# microInv_batt_controller.net
KiCad netlist of a schematic drawn in Altium Designer
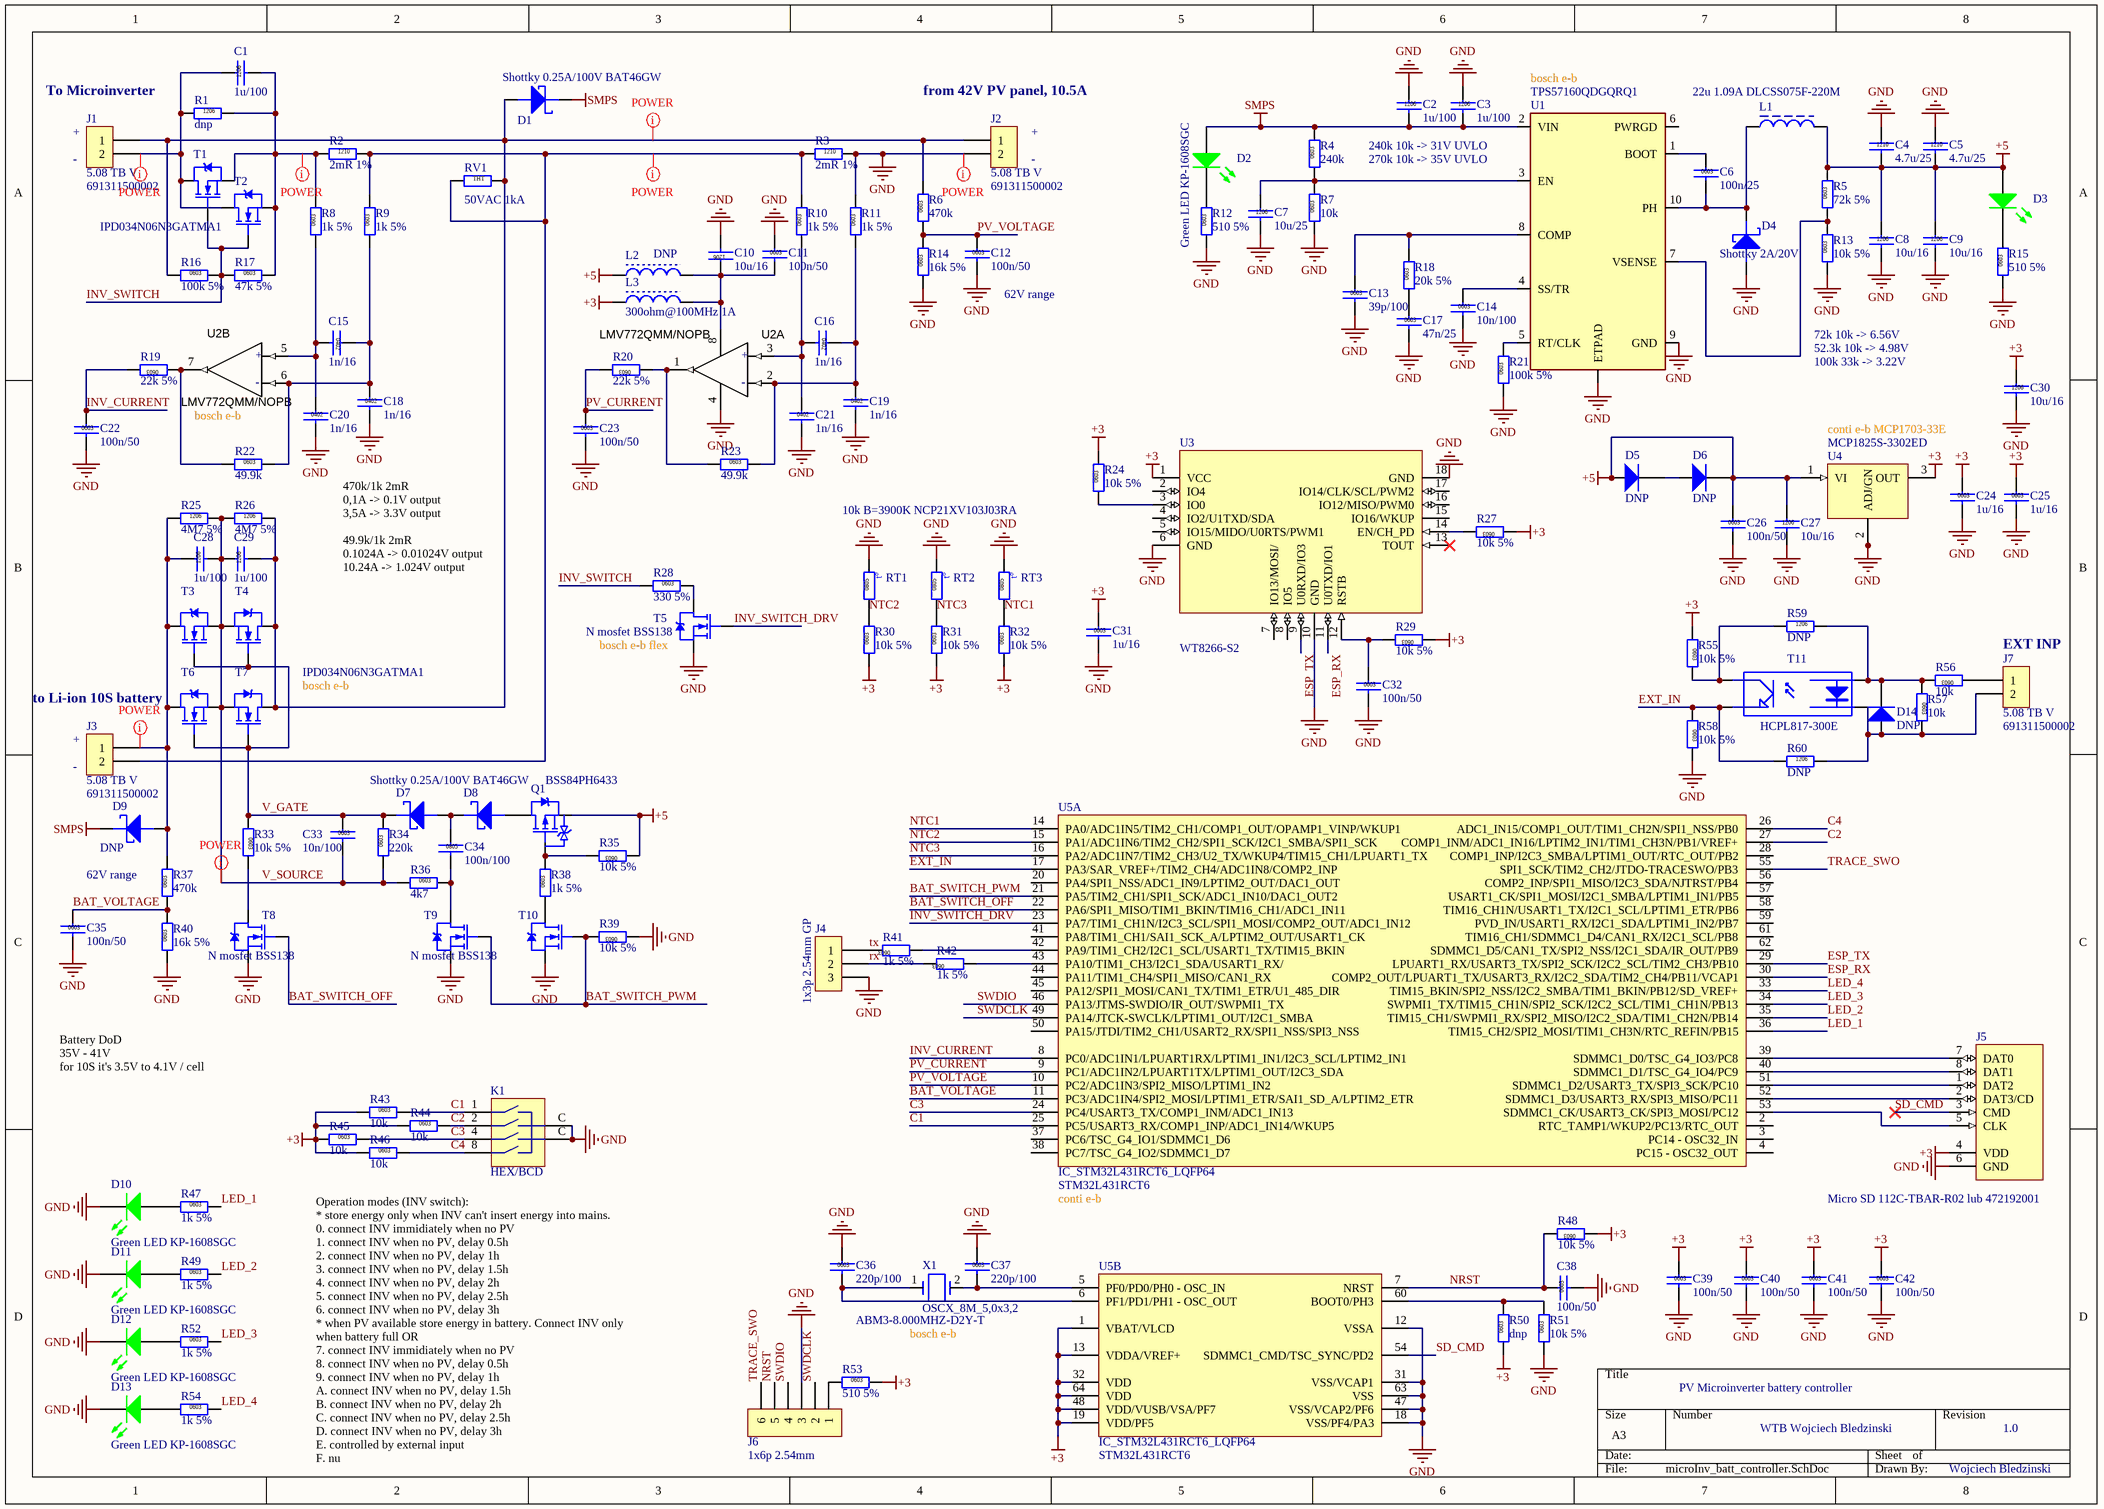
[diagram p0: microInv_batt_controller.SchDoc]

(export (version "E")
  (design (tool "Eeschema 10.0.6"))
  (components
    (comp (ref "C1")
      (value "1u/100")
      (footprint "CAP_1206")
      (description "X7R chip capacitor")
      (fields (field (name "MANUFACTURER") "AVX") (field (name "MANUFACTURER PART NUMBER") "12061C105KAT2A"))
      (libsource (lib "WB") (part "CAP_B_1u_100_1206_X7R"))
    )
    (comp (ref "C2")
      (value "1u/100")
      (footprint "CAP_1206")
      (description "X7R chip capacitor")
      (fields (field (name "MANUFACTURER") "AVX") (field (name "MANUFACTURER PART NUMBER") "12061C105KAT2A"))
      (libsource (lib "WB") (part "CAP_B_1u_100_1206_X7R"))
    )
    (comp (ref "C3")
      (value "1u/100")
      (footprint "CAP_1206")
      (description "X7R chip capacitor")
      (fields (field (name "MANUFACTURER") "AVX") (field (name "MANUFACTURER PART NUMBER") "12061C105KAT2A"))
      (libsource (lib "WB") (part "CAP_B_1u_100_1206_X7R"))
    )
    (comp (ref "C4")
      (value "4.7u/25")
      (footprint "CAP_1210")
      (description "X5R chip capacitor")
      (fields
        (field (name "MANUFACTURER") "YAGEO")
        (field (name "MANUFACTURER PART NUMBER") "CC1210KKX5R8BB475")
      )
      (libsource (lib "WB") (part "CAP_B_4.7u_25_1210_X5R"))
    )
    (comp (ref "C5")
      (value "4.7u/25")
      (footprint "CAP_1210")
      (description "X5R chip capacitor")
      (fields
        (field (name "MANUFACTURER") "YAGEO")
        (field (name "MANUFACTURER PART NUMBER") "CC1210KKX5R8BB475")
      )
      (libsource (lib "WB") (part "CAP_B_4.7u_25_1210_X5R"))
    )
    (comp (ref "C6")
      (value "100n/25")
      (footprint "CAP_0603")
      (description "X7R chip capacitor")
      (fields
        (field (name "MANUFACTURER") "SAMSUNG")
        (field (name "MANUFACTURER PART NUMBER") "CL10B104KB8NNNC")
      )
      (libsource (lib "WB") (part "CAP_B_100n_50_0603_X7R"))
    )
    (comp (ref "C7")
      (value "10u/25")
      (footprint "CAP_1206")
      (description "X5R chip capacitor")
      (fields
        (field (name "MANUFACTURER") "SAMSUNG")
        (field (name "MANUFACTURER PART NUMBER") "CL31A106KAHNNNE")
      )
      (libsource (lib "WB") (part "CAP_B_10u_25_1206_X5R"))
    )
    (comp (ref "C8")
      (value "10u/16")
      (footprint "CAP_1206")
      (description "X7R chip capacitor")
      (fields
        (field (name "MANUFACTURER") "KYOCERA")
        (field (name "MANUFACTURER PART NUMBER") "CM316X7R106K16AT")
      )
      (libsource (lib "WB") (part "CAP_B_10u_16_1206_X7R"))
    )
    (comp (ref "C9")
      (value "10u/16")
      (footprint "CAP_1206")
      (description "X7R chip capacitor")
      (fields
        (field (name "MANUFACTURER") "KYOCERA")
        (field (name "MANUFACTURER PART NUMBER") "CM316X7R106K16AT")
      )
      (libsource (lib "WB") (part "CAP_B_10u_16_1206_X7R"))
    )
    (comp (ref "C10")
      (value "10u/16")
      (footprint "CAP_1206")
      (description "X7R chip capacitor")
      (fields
        (field (name "MANUFACTURER") "KYOCERA")
        (field (name "MANUFACTURER PART NUMBER") "CM316X7R106K16AT")
      )
      (libsource (lib "WB") (part "CAP_B_10u_16_1206_X7R"))
    )
    (comp (ref "C11")
      (value "100n/50")
      (footprint "CAP_0603")
      (description "X7R chip capacitor")
      (fields
        (field (name "MANUFACTURER") "SAMSUNG")
        (field (name "MANUFACTURER PART NUMBER") "CL10B104KB8NNNC")
      )
      (libsource (lib "WB") (part "CAP_B_100n_50_0603_X7R"))
    )
    (comp (ref "C12")
      (value "100n/50")
      (footprint "CAP_0603")
      (description "X7R chip capacitor")
      (fields
        (field (name "MANUFACTURER") "SAMSUNG")
        (field (name "MANUFACTURER PART NUMBER") "CL10B104KB8NNNC")
      )
      (libsource (lib "WB") (part "CAP_B_100n_50_0603_X7R"))
    )
    (comp (ref "C13")
      (value "39p/100")
      (footprint "CAP_0603")
      (description "COG chip capacitor")
      (fields (field (name "TOLERANCE") "10%") (field (name "VOLTAGE") "100"))
      (libsource (lib "WB") (part "CAP_B_39p_100_0603_COG"))
    )
    (comp (ref "C14")
      (value "10n/100")
      (footprint "CAP_0603")
      (description "X7R chip capacitor")
      (fields
        (field (name "MANUFACTURER") "SAMSUNG")
        (field (name "MANUFACTURER PART NUMBER") "CL10B103KC8NNNC")
      )
      (libsource (lib "WB") (part "CAP_B_10n_100_0603_X7R"))
    )
    (comp (ref "C15")
      (value "1n/16")
      (footprint "CAP_0402_HD_IPC")
      (description "X7R chip capacitor")
      (fields
        (field (name "MANUFACTURER") "SAMSUNG")
        (field (name "MANUFACTURER PART NUMBER") "0402YC102KAT2A")
      )
      (libsource (lib "WB") (part "CAP_B_1n_16_0402_X7R"))
    )
    (comp (ref "C16")
      (value "1n/16")
      (footprint "CAP_0402_HD_IPC")
      (description "X7R chip capacitor")
      (fields
        (field (name "MANUFACTURER") "SAMSUNG")
        (field (name "MANUFACTURER PART NUMBER") "0402YC102KAT2A")
      )
      (libsource (lib "WB") (part "CAP_B_1n_16_0402_X7R"))
    )
    (comp (ref "C17")
      (value "47n/25")
      (footprint "CAP_0603")
      (description "X7R chip capacitor")
      (fields (field (name "TOLERANCE") "10%") (field (name "VOLTAGE") "25"))
      (libsource (lib "WB") (part "CAP_B_47n_25_0603_X7R"))
    )
    (comp (ref "C18")
      (value "1n/16")
      (footprint "CAP_0402_HD_IPC")
      (description "X7R chip capacitor")
      (fields
        (field (name "MANUFACTURER") "SAMSUNG")
        (field (name "MANUFACTURER PART NUMBER") "0402YC102KAT2A")
      )
      (libsource (lib "WB") (part "CAP_B_1n_16_0402_X7R"))
    )
    (comp (ref "C19")
      (value "1n/16")
      (footprint "CAP_0402_HD_IPC")
      (description "X7R chip capacitor")
      (fields
        (field (name "MANUFACTURER") "SAMSUNG")
        (field (name "MANUFACTURER PART NUMBER") "0402YC102KAT2A")
      )
      (libsource (lib "WB") (part "CAP_B_1n_16_0402_X7R"))
    )
    (comp (ref "C20")
      (value "1n/16")
      (footprint "CAP_0402_HD_IPC")
      (description "X7R chip capacitor")
      (fields
        (field (name "MANUFACTURER") "SAMSUNG")
        (field (name "MANUFACTURER PART NUMBER") "0402YC102KAT2A")
      )
      (libsource (lib "WB") (part "CAP_B_1n_16_0402_X7R"))
    )
    (comp (ref "C21")
      (value "1n/16")
      (footprint "CAP_0402_HD_IPC")
      (description "X7R chip capacitor")
      (fields
        (field (name "MANUFACTURER") "SAMSUNG")
        (field (name "MANUFACTURER PART NUMBER") "0402YC102KAT2A")
      )
      (libsource (lib "WB") (part "CAP_B_1n_16_0402_X7R"))
    )
    (comp (ref "C22")
      (value "100n/50")
      (footprint "CAP_0603")
      (description "X7R chip capacitor")
      (fields
        (field (name "MANUFACTURER") "SAMSUNG")
        (field (name "MANUFACTURER PART NUMBER") "CL10B104KB8NNNC")
      )
      (libsource (lib "WB") (part "CAP_B_100n_50_0603_X7R"))
    )
    (comp (ref "C23")
      (value "100n/50")
      (footprint "CAP_0603")
      (description "X7R chip capacitor")
      (fields
        (field (name "MANUFACTURER") "SAMSUNG")
        (field (name "MANUFACTURER PART NUMBER") "CL10B104KB8NNNC")
      )
      (libsource (lib "WB") (part "CAP_B_100n_50_0603_X7R"))
    )
    (comp (ref "C24")
      (value "1u/16")
      (footprint "CAP_0603")
      (description "X7R chip capacitor")
      (fields
        (field (name "MANUFACTURER") "SAMSUNG")
        (field (name "MANUFACTURER PART NUMBER") "CL10B105KO8NNNC")
      )
      (libsource (lib "WB") (part "CAP_B_1u_16_0603_X7R"))
    )
    (comp (ref "C25")
      (value "1u/16")
      (footprint "CAP_0603")
      (description "X7R chip capacitor")
      (fields
        (field (name "MANUFACTURER") "SAMSUNG")
        (field (name "MANUFACTURER PART NUMBER") "CL10B105KO8NNNC")
      )
      (libsource (lib "WB") (part "CAP_B_1u_16_0603_X7R"))
    )
    (comp (ref "C26")
      (value "100n/50")
      (footprint "CAP_0603")
      (description "X7R chip capacitor")
      (fields
        (field (name "MANUFACTURER") "SAMSUNG")
        (field (name "MANUFACTURER PART NUMBER") "CL10B104KB8NNNC")
      )
      (libsource (lib "WB") (part "CAP_B_100n_50_0603_X7R"))
    )
    (comp (ref "C27")
      (value "10u/16")
      (footprint "CAP_1206")
      (description "X7R chip capacitor")
      (fields
        (field (name "MANUFACTURER") "KYOCERA")
        (field (name "MANUFACTURER PART NUMBER") "CM316X7R106K16AT")
      )
      (libsource (lib "WB") (part "CAP_B_10u_16_1206_X7R"))
    )
    (comp (ref "C28")
      (value "1u/100")
      (footprint "CAP_1206")
      (description "X7R chip capacitor")
      (fields (field (name "MANUFACTURER") "AVX") (field (name "MANUFACTURER PART NUMBER") "12061C105KAT2A"))
      (libsource (lib "WB") (part "CAP_B_1u_100_1206_X7R"))
    )
    (comp (ref "C29")
      (value "1u/100")
      (footprint "CAP_1206")
      (description "X7R chip capacitor")
      (fields (field (name "MANUFACTURER") "AVX") (field (name "MANUFACTURER PART NUMBER") "12061C105KAT2A"))
      (libsource (lib "WB") (part "CAP_B_1u_100_1206_X7R"))
    )
    (comp (ref "C30")
      (value "10u/16")
      (footprint "CAP_1206")
      (description "X7R chip capacitor")
      (fields
        (field (name "MANUFACTURER") "KYOCERA")
        (field (name "MANUFACTURER PART NUMBER") "CM316X7R106K16AT")
      )
      (libsource (lib "WB") (part "CAP_B_10u_16_1206_X7R"))
    )
    (comp (ref "C31")
      (value "1u/16")
      (footprint "CAP_0603")
      (description "X7R chip capacitor")
      (fields
        (field (name "MANUFACTURER") "SAMSUNG")
        (field (name "MANUFACTURER PART NUMBER") "CL10B105KO8NNNC")
      )
      (libsource (lib "WB") (part "CAP_B_1u_16_0603_X7R"))
    )
    (comp (ref "C32")
      (value "100n/50")
      (footprint "CAP_0603")
      (description "X7R chip capacitor")
      (fields
        (field (name "MANUFACTURER") "SAMSUNG")
        (field (name "MANUFACTURER PART NUMBER") "CL10B104KB8NNNC")
      )
      (libsource (lib "WB") (part "CAP_B_100n_50_0603_X7R"))
    )
    (comp (ref "C33")
      (value "10n/100")
      (footprint "CAP_0603")
      (description "X7R chip capacitor")
      (fields
        (field (name "MANUFACTURER") "SAMSUNG")
        (field (name "MANUFACTURER PART NUMBER") "CL10B103KC8NNNC")
      )
      (libsource (lib "WB") (part "CAP_B_10n_100_0603_X7R"))
    )
    (comp (ref "C34")
      (value "100n/100")
      (footprint "CAP_0805")
      (description "X7R chip capacitor")
      (fields (field (name "MANUFACTURER") "AVX") (field (name "MANUFACTURER PART NUMBER") "08051C104KAZ2A"))
      (libsource (lib "WB") (part "CAP_B_100n_100_0805_X7R"))
    )
    (comp (ref "C35")
      (value "100n/50")
      (footprint "CAP_0603")
      (description "X7R chip capacitor")
      (fields
        (field (name "MANUFACTURER") "SAMSUNG")
        (field (name "MANUFACTURER PART NUMBER") "CL10B104KB8NNNC")
      )
      (libsource (lib "WB") (part "CAP_B_100n_50_0603_X7R"))
    )
    (comp (ref "C36")
      (value "220p/100")
      (footprint "CAP_0603")
      (description "COG chip capacitor")
      (fields
        (field (name "MANUFACTURER") "SAMSUNG")
        (field (name "MANUFACTURER PART NUMBER") "CL10C221JB8NNNC")
      )
      (libsource (lib "WB") (part "CAP_B_220p_100_0603_COG"))
    )
    (comp (ref "C37")
      (value "220p/100")
      (footprint "CAP_0603")
      (description "COG chip capacitor")
      (fields
        (field (name "MANUFACTURER") "SAMSUNG")
        (field (name "MANUFACTURER PART NUMBER") "CL10C221JB8NNNC")
      )
      (libsource (lib "WB") (part "CAP_B_220p_100_0603_COG"))
    )
    (comp (ref "C38")
      (value "100n/50")
      (footprint "CAP_0603")
      (description "X7R chip capacitor")
      (fields
        (field (name "MANUFACTURER") "SAMSUNG")
        (field (name "MANUFACTURER PART NUMBER") "CL10B104KB8NNNC")
      )
      (libsource (lib "WB") (part "CAP_B_100n_50_0603_X7R"))
    )
    (comp (ref "C39")
      (value "100n/50")
      (footprint "CAP_0603")
      (description "X7R chip capacitor")
      (fields
        (field (name "MANUFACTURER") "SAMSUNG")
        (field (name "MANUFACTURER PART NUMBER") "CL10B104KB8NNNC")
      )
      (libsource (lib "WB") (part "CAP_B_100n_50_0603_X7R"))
    )
    (comp (ref "C40")
      (value "100n/50")
      (footprint "CAP_0603")
      (description "X7R chip capacitor")
      (fields
        (field (name "MANUFACTURER") "SAMSUNG")
        (field (name "MANUFACTURER PART NUMBER") "CL10B104KB8NNNC")
      )
      (libsource (lib "WB") (part "CAP_B_100n_50_0603_X7R"))
    )
    (comp (ref "C41")
      (value "100n/50")
      (footprint "CAP_0603")
      (description "X7R chip capacitor")
      (fields
        (field (name "MANUFACTURER") "SAMSUNG")
        (field (name "MANUFACTURER PART NUMBER") "CL10B104KB8NNNC")
      )
      (libsource (lib "WB") (part "CAP_B_100n_50_0603_X7R"))
    )
    (comp (ref "C42")
      (value "100n/50")
      (footprint "CAP_0603")
      (description "X7R chip capacitor")
      (fields
        (field (name "MANUFACTURER") "SAMSUNG")
        (field (name "MANUFACTURER PART NUMBER") "CL10B104KB8NNNC")
      )
      (libsource (lib "WB") (part "CAP_B_100n_50_0603_X7R"))
    )
    (comp (ref "D1")
      (value "Shottky 0.25A/100V BAT46GW")
      (footprint "SOD_123")
      (description "Shottky Diode trr 4ns 0,43V @ 0.05A 0.75V@0.25A")
      (fields
        (field (name "MANUFACTURER") "Nexperia")
        (field (name "MANUFACTURER PART NUMBER") "BAT46GWX 934070363115")
      )
      (libsource (lib "WB") (part "D_0.25_100_BAT46GWX"))
    )
    (comp (ref "D2")
      (value "Green LED KP-1608SGC")
      (footprint "LED_0603_GREEN")
      (description "Diode LED SMD 2.2V @ 20mA 15mcd")
      (fields
        (field (name "MANUFACTURER") "KINGBRIGHT")
        (field (name "MANUFACTURER PART NUMBER") "KP-1608SGC")
      )
      (libsource (lib "WB") (part "D_LED_0603_GREEN"))
    )
    (comp (ref "D3")
      (value "Green LED KP-1608SGC")
      (footprint "LED_0603_GREEN")
      (description "Diode LED SMD 2.2V @ 20mA 15mcd")
      (fields
        (field (name "MANUFACTURER") "KINGBRIGHT")
        (field (name "MANUFACTURER PART NUMBER") "KP-1608SGC")
      )
      (libsource (lib "WB") (part "D_LED_0603_GREEN"))
    )
    (comp (ref "D4")
      (value "Shottky 2A/20V")
      (footprint "SMA_DO-214AC")
      (description "Shottky Diode 0,5V @ 2A SMA 200pF")
      (fields (field (name "MANUFACTURER") "DIODES") (field (name "MANUFACTURER PART NUMBER") "B220A-13-F"))
      (libsource (lib "WB") (part "D_2A_20_B220A"))
    )
    (comp (ref "D5")
      (value "DNP")
      (footprint "D_MINIMELF")
      (fields
        (field (name "MANUFACTURER") "ON SEMICONDUCTOR (FAIRCHILD)")
        (field (name "MANUFACTURER PART NUMBER") "FDLL4148")
      )
      (libsource (lib "WB") (part "D_LL4148_MMELF"))
    )
    (comp (ref "D6")
      (value "DNP")
      (footprint "D_MINIMELF")
      (fields
        (field (name "MANUFACTURER") "ON SEMICONDUCTOR (FAIRCHILD)")
        (field (name "MANUFACTURER PART NUMBER") "FDLL4148")
      )
      (libsource (lib "WB") (part "D_LL4148_MMELF"))
    )
    (comp (ref "D7")
      (value "Shottky 0.25A/100V BAT46GW")
      (footprint "SOD_123")
      (description "Shottky Diode trr 4ns 0,43V @ 0.05A 0.75V@0.25A")
      (fields
        (field (name "MANUFACTURER") "Nexperia")
        (field (name "MANUFACTURER PART NUMBER") "BAT46GWX 934070363115")
      )
      (libsource (lib "WB") (part "D_0.25_100_BAT46GWX"))
    )
    (comp (ref "D8")
      (value "Shottky 0.25A/100V BAT46GW")
      (footprint "SOD_123")
      (description "Shottky Diode trr 4ns 0,43V @ 0.05A 0.75V@0.25A")
      (fields
        (field (name "MANUFACTURER") "Nexperia")
        (field (name "MANUFACTURER PART NUMBER") "BAT46GWX 934070363115")
      )
      (libsource (lib "WB") (part "D_0.25_100_BAT46GWX"))
    )
    (comp (ref "D9")
      (value "DNP")
      (footprint "SOD_123")
      (description "Shottky Diode trr 4ns 0,43V @ 0.05A 0.75V@0.25A")
      (fields
        (field (name "MANUFACTURER") "Nexperia")
        (field (name "MANUFACTURER PART NUMBER") "BAT46GWX 934070363115")
      )
      (libsource (lib "WB") (part "D_0.25_100_BAT46GWX"))
    )
    (comp (ref "D10")
      (value "Green LED KP-1608SGC")
      (footprint "LED_0603_GREEN")
      (description "Diode LED SMD 2.2V @ 20mA 15mcd")
      (fields
        (field (name "MANUFACTURER") "KINGBRIGHT")
        (field (name "MANUFACTURER PART NUMBER") "KP-1608SGC")
      )
      (libsource (lib "WB") (part "D_LED_0603_GREEN"))
    )
    (comp (ref "D11")
      (value "Green LED KP-1608SGC")
      (footprint "LED_0603_GREEN")
      (description "Diode LED SMD 2.2V @ 20mA 15mcd")
      (fields
        (field (name "MANUFACTURER") "KINGBRIGHT")
        (field (name "MANUFACTURER PART NUMBER") "KP-1608SGC")
      )
      (libsource (lib "WB") (part "D_LED_0603_GREEN"))
    )
    (comp (ref "D12")
      (value "Green LED KP-1608SGC")
      (footprint "LED_0603_GREEN")
      (description "Diode LED SMD 2.2V @ 20mA 15mcd")
      (fields
        (field (name "MANUFACTURER") "KINGBRIGHT")
        (field (name "MANUFACTURER PART NUMBER") "KP-1608SGC")
      )
      (libsource (lib "WB") (part "D_LED_0603_GREEN"))
    )
    (comp (ref "D13")
      (value "Green LED KP-1608SGC")
      (footprint "LED_0603_GREEN")
      (description "Diode LED SMD 2.2V @ 20mA 15mcd")
      (fields
        (field (name "MANUFACTURER") "KINGBRIGHT")
        (field (name "MANUFACTURER PART NUMBER") "KP-1608SGC")
      )
      (libsource (lib "WB") (part "D_LED_0603_GREEN"))
    )
    (comp (ref "D14")
      (value "DNP")
      (footprint "D_MINIMELF")
      (fields
        (field (name "MANUFACTURER") "ON SEMICONDUCTOR (FAIRCHILD)")
        (field (name "MANUFACTURER PART NUMBER") "FDLL4148")
      )
      (libsource (lib "WB") (part "D_LL4148_MMELF"))
    )
    (comp (ref "J1")
      (value "5.08 TB V")
      (footprint "CON_1x2_5.08TB")
      (description "THT 5,08mm, WE 691311500002 (rev1), NINIGI , MLX")
      (fields
        (field (name "MANUFACTURER") "Wurth Electronics")
        (field (name "MANUFACTURER PART NUMBER") "691311500002")
      )
      (libsource (lib "WB") (part "CON_1x2_TB_5.08V"))
    )
    (comp (ref "J2")
      (value "5.08 TB V")
      (footprint "CON_1x2_5.08TB")
      (description "THT 5,08mm, WE 691311500002 (rev1), NINIGI , MLX")
      (fields
        (field (name "MANUFACTURER") "Wurth Electronics")
        (field (name "MANUFACTURER PART NUMBER") "691311500002")
      )
      (libsource (lib "") (part "CON_1x2_TB_5.08V_1"))
    )
    (comp (ref "J3")
      (value "5.08 TB V")
      (footprint "CON_1x2_5.08TB")
      (description "THT 5,08mm, WE 691311500002 (rev1), NINIGI , MLX")
      (fields
        (field (name "MANUFACTURER") "Wurth Electronics")
        (field (name "MANUFACTURER PART NUMBER") "691311500002")
      )
      (libsource (lib "WB") (part "CON_1x2_TB_5.08V"))
    )
    (comp (ref "J4")
      (value "1x3p 2.54mm GP")
      (footprint "CON_PIN1x3_THT")
      (description "THT 2,54 goldpin")
      (fields (field (name "MANUFACTURER") "TME") (field (name "MANUFACTURER PART NUMBER") "ZL201-03G"))
      (libsource (lib "WB") (part "CON_1x3_GP_THT"))
    )
    (comp (ref "J5")
      (value "Micro SD 112C-TBAR-R02 lub 472192001")
      (footprint "112C_TXAR_R01")
      (description "Micro SD connector SMD, ATTEND 112C-TBAR-R02; MOLEX 472192001")
      (fields
        (field (name "MANUFACTURER") "ATTEND")
        (field (name "MANUFACTURER PART NUMBER") "112C-TBAR-R02")
      )
      (libsource (lib "WB") (part "CON_MicroSD"))
    )
    (comp (ref "J6")
      (value "1x6p 2.54mm")
      (footprint "CON_PIN1x6_THT")
      (description "THT 2,54 goldpin")
      (fields
        (field (name "MANUFACTURER") "CONNFLY")
        (field (name "MANUFACTURER PART NUMBER") "DS1021-1*6SF1-1")
      )
      (libsource (lib "WB") (part "CON_1x6_GP_THT"))
    )
    (comp (ref "J7")
      (value "5.08 TB V")
      (footprint "CON_1x2_5.08TB")
      (description "THT 5,08mm, WE 691311500002 (rev1), NINIGI , MLX")
      (fields
        (field (name "MANUFACTURER") "Wurth Electronics")
        (field (name "MANUFACTURER PART NUMBER") "691311500002")
      )
      (libsource (lib "") (part "CON_1x2_TB_5.08V_1"))
    )
    (comp (ref "K1")
      (value "HEX/BCD")
      (footprint "MECH_SW_HEXBCD")
      (description "Zadajnik kodu")
      (fields (field (name "MANUFACTURER") "ECE") (field (name "MANUFACTURER PART NUMBER") "ERD116RSZ"))
      (libsource (lib "WB") (part "MECH_SW_HEXBCD"))
    )
    (comp (ref "L1")
      (value "22u 1.09A DLCSS075F-220M")
      (footprint "IND_DER0705")
      (description "shielded power inductor 1.09A Rdc=0,12")
      (fields
        (field (name "MANUFACTURER") "FERROCORE")
        (field (name "MANUFACTURER PART NUMBER") "DER0705-22")
      )
      (libsource (lib "WB") (part "IND_22u_1.09A_DER0705-22"))
    )
    (comp (ref "L2")
      (value "DNP")
      (footprint "RES_0603")
      (description "2A Rdc=0,15 SRF 250MHz")
      (fields (field (name "MANUFACTURER") "WE") (field (name "MANUFACTURER PART NUMBER") "742792641"))
      (libsource (lib "WB") (part "IND_FB_300R_0603"))
    )
    (comp (ref "L3")
      (value "300ohm@100MHz 1A")
      (footprint "RES_0603")
      (description "2A Rdc=0,15 SRF 250MHz")
      (fields (field (name "MANUFACTURER") "WE") (field (name "MANUFACTURER PART NUMBER") "742792641"))
      (libsource (lib "WB") (part "IND_FB_300R_0603"))
    )
    (comp (ref "Q1")
      (value "BSS84PH6433")
      (footprint "SOT23-3")
      (description "50V 130mA P Mosfet")
      (fields (field (name "MANUFACTURER") "INFINEON TECHNOLOGIES") (field (name "POWER") "360mW"))
      (libsource (lib "WB") (part "T_BSS84"))
    )
    (comp (ref "R1")
      (value "dnp")
      (footprint "RES_1206")
      (description "Resistor 1206 5% 0,25W")
      (fields
        (field (name "MANUFACTURER") "ROYAL OHM")
        (field (name "MANUFACTURER PART NUMBER") "1206S4J0000T5E")
      )
      (libsource (lib "WB") (part "RES_0R_5p_1206"))
    )
    (comp (ref "R2")
      (value "2mR 1%")
      (footprint "RES_1210")
      (description "Resistor 1210 5% 0,5W")
      (fields (field (name "TOLERANCE") "5%") (field (name "VOLTAGE") "500"))
      (libsource (lib "WB") (part "RES_2R2_5p_1210"))
    )
    (comp (ref "R3")
      (value "2mR 1%")
      (footprint "RES_1210")
      (description "Resistor 1210 5% 0,5W")
      (fields (field (name "TOLERANCE") "5%") (field (name "VOLTAGE") "500"))
      (libsource (lib "WB") (part "RES_2R2_5p_1210"))
    )
    (comp (ref "R4")
      (value "240k")
      (footprint "RES_0603")
      (description "Resistor 0603 5% 0,1W")
      (fields (field (name "TOLERANCE") "5%") (field (name "VOLTAGE") "50"))
      (libsource (lib "WB") (part "RES_105k_5p_0603"))
    )
    (comp (ref "R5")
      (value "72k 5%")
      (footprint "RES_0603")
      (description "Resistor 0603 5% 0,1W")
      (fields
        (field (name "MANUFACTURER") "YAGEO")
        (field (name "MANUFACTURER PART NUMBER") "RC0603JR-0762K")
      )
      (libsource (lib "WB") (part "RES_62k_5p_0603"))
    )
    (comp (ref "R6")
      (value "470k")
      (footprint "RES_0603")
      (description "Resistor 0603 5% 0,1W")
      (fields (field (name "MANUFACTURER") "YAGEO") (field (name "TOLERANCE") "5%"))
      (libsource (lib "") (part "RES_1k_5p_0603_1"))
    )
    (comp (ref "R7")
      (value "10k")
      (footprint "RES_0603")
      (description "Resistor 0603 5% 0,1W")
      (fields (field (name "MANUFACTURER") "YAGEO") (field (name "TOLERANCE") "5%"))
      (libsource (lib "") (part "RES_16k_5p_0603_2"))
    )
    (comp (ref "R8")
      (value "1k 5%")
      (footprint "RES_0603")
      (description "Resistor 0603 5% 0,1W")
      (fields (field (name "MANUFACTURER") "YAGEO") (field (name "TOLERANCE") "5%"))
      (libsource (lib "") (part "RES_1k_5p_0603_1"))
    )
    (comp (ref "R9")
      (value "1k 5%")
      (footprint "RES_0603")
      (description "Resistor 0603 5% 0,1W")
      (fields (field (name "MANUFACTURER") "YAGEO") (field (name "TOLERANCE") "5%"))
      (libsource (lib "") (part "RES_1k_5p_0603_1"))
    )
    (comp (ref "R10")
      (value "1k 5%")
      (footprint "RES_0603")
      (description "Resistor 0603 5% 0,1W")
      (fields (field (name "MANUFACTURER") "YAGEO") (field (name "TOLERANCE") "5%"))
      (libsource (lib "") (part "RES_1k_5p_0603_1"))
    )
    (comp (ref "R11")
      (value "1k 5%")
      (footprint "RES_0603")
      (description "Resistor 0603 5% 0,1W")
      (fields (field (name "MANUFACTURER") "YAGEO") (field (name "TOLERANCE") "5%"))
      (libsource (lib "") (part "RES_1k_5p_0603_1"))
    )
    (comp (ref "R12")
      (value "510 5%")
      (footprint "RES_0603")
      (description "Resistor 0603 5% 0,1W")
      (fields (field (name "TOLERANCE") "5%") (field (name "VOLTAGE") "50"))
      (libsource (lib "WB") (part "RES_510_5p_0603"))
    )
    (comp (ref "R13")
      (value "10k 5%")
      (footprint "RES_0603")
      (description "Resistor 0603 5% 0,1W")
      (fields (field (name "TOLERANCE") "5%") (field (name "VOLTAGE") "50"))
      (libsource (lib "") (part "RES_10k_5p_0603_2"))
    )
    (comp (ref "R14")
      (value "16k 5%")
      (footprint "RES_0603")
      (description "Resistor 0603 5% 0,1W")
      (fields (field (name "MANUFACTURER") "YAGEO") (field (name "TOLERANCE") "5%"))
      (libsource (lib "") (part "RES_16k_5p_0603_2"))
    )
    (comp (ref "R15")
      (value "510 5%")
      (footprint "RES_0603")
      (description "Resistor 0603 5% 0,1W")
      (fields (field (name "TOLERANCE") "5%") (field (name "VOLTAGE") "50"))
      (libsource (lib "WB") (part "RES_510_5p_0603"))
    )
    (comp (ref "R16")
      (value "100k 5%")
      (footprint "RES_0603")
      (description "Resistor 0603 5% 0,1W")
      (fields (field (name "TOLERANCE") "5%") (field (name "VOLTAGE") "50"))
      (libsource (lib "") (part "RES_100k_5p_0603_1"))
    )
    (comp (ref "R17")
      (value "47k 5%")
      (footprint "RES_0603")
      (description "Resistor 0603 5% 0,1W")
      (fields (field (name "MANUFACTURER") "YAGEO") (field (name "TOLERANCE") "5%"))
      (libsource (lib "WB") (part "RES_47k_5p_0603"))
    )
    (comp (ref "R18")
      (value "20k 5%")
      (footprint "RES_0603")
      (description "Resistor 0603 5% 0,1W")
      (fields
        (field (name "MANUFACTURER") "ROYAL OHM")
        (field (name "MANUFACTURER PART NUMBER") "0603SAJ0203T5E")
      )
      (libsource (lib "WB") (part "RES_20k_5p_0603"))
    )
    (comp (ref "R19")
      (value "22k 5%")
      (footprint "RES_0603")
      (description "Resistor 0603 5% 0,1W")
      (fields (field (name "MANUFACTURER") "YAGEO") (field (name "TOLERANCE") "5%"))
      (libsource (lib "WB") (part "RES_22k_5p_0603"))
    )
    (comp (ref "R20")
      (value "22k 5%")
      (footprint "RES_0603")
      (description "Resistor 0603 5% 0,1W")
      (fields (field (name "MANUFACTURER") "YAGEO") (field (name "TOLERANCE") "5%"))
      (libsource (lib "WB") (part "RES_22k_5p_0603"))
    )
    (comp (ref "R21")
      (value "100k 5%")
      (footprint "RES_0603")
      (description "Resistor 0603 5% 0,1W")
      (fields (field (name "TOLERANCE") "5%") (field (name "VOLTAGE") "50"))
      (libsource (lib "WB") (part "RES_100k_5p_0603"))
    )
    (comp (ref "R22")
      (value "49.9k")
      (footprint "RES_0603")
      (description "Resistor 0603 5% 0,1W")
      (fields (field (name "MANUFACTURER") "YAGEO") (field (name "TOLERANCE") "5%"))
      (libsource (lib "WB") (part "RES_1k_5p_0603"))
    )
    (comp (ref "R23")
      (value "49.9k")
      (footprint "RES_0603")
      (description "Resistor 0603 5% 0,1W")
      (fields (field (name "MANUFACTURER") "YAGEO") (field (name "TOLERANCE") "5%"))
      (libsource (lib "WB") (part "RES_1k_5p_0603"))
    )
    (comp (ref "R24")
      (value "10k 5%")
      (footprint "RES_0603")
      (description "Resistor 0603 5% 0,1W")
      (fields (field (name "TOLERANCE") "5%") (field (name "VOLTAGE") "50"))
      (libsource (lib "") (part "RES_10k_5p_0603_2"))
    )
    (comp (ref "R25")
      (value "4M7 5%")
      (footprint "RES_1206")
      (description "Resistor 1206 5% 0,25W")
      (fields
        (field (name "MANUFACTURER") "ROYAL OHM")
        (field (name "MANUFACTURER PART NUMBER") "1206S4J0475T5E")
      )
      (libsource (lib "WB") (part "RES_4M7_5p_1206"))
    )
    (comp (ref "R26")
      (value "4M7 5%")
      (footprint "RES_1206")
      (description "Resistor 1206 5% 0,25W")
      (fields
        (field (name "MANUFACTURER") "ROYAL OHM")
        (field (name "MANUFACTURER PART NUMBER") "1206S4J0475T5E")
      )
      (libsource (lib "WB") (part "RES_4M7_5p_1206"))
    )
    (comp (ref "R27")
      (value "10k 5%")
      (footprint "RES_0603")
      (description "Resistor 0603 5% 0,1W")
      (fields (field (name "TOLERANCE") "5%") (field (name "VOLTAGE") "50"))
      (libsource (lib "WB") (part "RES_10k_5p_0603"))
    )
    (comp (ref "R28")
      (value "330 5%")
      (footprint "RES_0603")
      (description "Resistor 0603 5% 0,1W")
      (fields (field (name "TOLERANCE") "5%") (field (name "VOLTAGE") "50"))
      (libsource (lib "WB") (part "RES_330R_5p_0603"))
    )
    (comp (ref "R29")
      (value "10k 5%")
      (footprint "RES_0603")
      (description "Resistor 0603 5% 0,1W")
      (fields (field (name "TOLERANCE") "5%") (field (name "VOLTAGE") "50"))
      (libsource (lib "WB") (part "RES_10k_5p_0603"))
    )
    (comp (ref "R30")
      (value "10k 5%")
      (footprint "RES_0603")
      (description "Resistor 0603 5% 0,1W")
      (fields (field (name "TOLERANCE") "5%") (field (name "VOLTAGE") "50"))
      (libsource (lib "") (part "RES_10k_5p_0603_2"))
    )
    (comp (ref "R31")
      (value "10k 5%")
      (footprint "RES_0603")
      (description "Resistor 0603 5% 0,1W")
      (fields (field (name "TOLERANCE") "5%") (field (name "VOLTAGE") "50"))
      (libsource (lib "") (part "RES_10k_5p_0603_2"))
    )
    (comp (ref "R32")
      (value "10k 5%")
      (footprint "RES_0603")
      (description "Resistor 0603 5% 0,1W")
      (fields (field (name "TOLERANCE") "5%") (field (name "VOLTAGE") "50"))
      (libsource (lib "") (part "RES_10k_5p_0603_2"))
    )
    (comp (ref "R33")
      (value "10k 5%")
      (footprint "RES_0603")
      (description "Resistor 0603 5% 0,1W")
      (fields (field (name "TOLERANCE") "5%") (field (name "VOLTAGE") "50"))
      (libsource (lib "") (part "RES_10k_5p_0603_1"))
    )
    (comp (ref "R34")
      (value "220k")
      (footprint "RES_0603")
      (description "Resistor 0603 5% 0,1W")
      (fields (field (name "TOLERANCE") "5%") (field (name "VOLTAGE") "50"))
      (libsource (lib "WB") (part "RES_100k_5p_0603"))
    )
    (comp (ref "R35")
      (value "10k 5%")
      (footprint "RES_0603")
      (description "Resistor 0603 5% 0,1W")
      (fields (field (name "TOLERANCE") "5%") (field (name "VOLTAGE") "50"))
      (libsource (lib "WB") (part "RES_10k_5p_0603"))
    )
    (comp (ref "R36")
      (value "4k7")
      (footprint "RES_0603")
      (description "Resistor 0603 5% 0,1W")
      (fields (field (name "TOLERANCE") "5%") (field (name "VOLTAGE") "50"))
      (libsource (lib "") (part "RES_100k_5p_0603_1"))
    )
    (comp (ref "R37")
      (value "470k")
      (footprint "RES_0603")
      (description "Resistor 0603 5% 0,1W")
      (fields (field (name "MANUFACTURER") "YAGEO") (field (name "TOLERANCE") "5%"))
      (libsource (lib "") (part "RES_1k_5p_0603_1"))
    )
    (comp (ref "R38")
      (value "1k 5%")
      (footprint "RES_0603")
      (description "Resistor 0603 5% 0,1W")
      (fields (field (name "MANUFACTURER") "YAGEO") (field (name "TOLERANCE") "5%"))
      (libsource (lib "") (part "RES_1k_5p_0603_1"))
    )
    (comp (ref "R39")
      (value "10k 5%")
      (footprint "RES_0603")
      (description "Resistor 0603 5% 0,1W")
      (fields (field (name "TOLERANCE") "5%") (field (name "VOLTAGE") "50"))
      (libsource (lib "WB") (part "RES_10k_5p_0603"))
    )
    (comp (ref "R40")
      (value "16k 5%")
      (footprint "RES_0603")
      (description "Resistor 0603 5% 0,1W")
      (fields (field (name "MANUFACTURER") "YAGEO") (field (name "TOLERANCE") "5%"))
      (libsource (lib "") (part "RES_16k_5p_0603_2"))
    )
    (comp (ref "R41")
      (value "1k 5%")
      (footprint "RES_0603")
      (description "Resistor 0603 5% 0,1W")
      (fields (field (name "MANUFACTURER") "YAGEO") (field (name "TOLERANCE") "5%"))
      (libsource (lib "") (part "RES_1k_5p_0603_1"))
    )
    (comp (ref "R42")
      (value "1k 5%")
      (footprint "RES_0603")
      (description "Resistor 0603 5% 0,1W")
      (fields (field (name "MANUFACTURER") "YAGEO") (field (name "TOLERANCE") "5%"))
      (libsource (lib "") (part "RES_1k_5p_0603_1"))
    )
    (comp (ref "R43")
      (value "10k")
      (footprint "RES_0603")
      (description "Resistor 0603 5% 0,1W")
      (fields (field (name "MANUFACTURER") "YAGEO") (field (name "TOLERANCE") "5%"))
      (libsource (lib "WB") (part "RES_16k_5p_0603"))
    )
    (comp (ref "R44")
      (value "10k")
      (footprint "RES_0603")
      (description "Resistor 0603 5% 0,1W")
      (fields (field (name "MANUFACTURER") "YAGEO") (field (name "TOLERANCE") "5%"))
      (libsource (lib "WB") (part "RES_16k_5p_0603"))
    )
    (comp (ref "R45")
      (value "10k")
      (footprint "RES_0603")
      (description "Resistor 0603 5% 0,1W")
      (fields (field (name "MANUFACTURER") "YAGEO") (field (name "TOLERANCE") "5%"))
      (libsource (lib "WB") (part "RES_16k_5p_0603"))
    )
    (comp (ref "R46")
      (value "10k")
      (footprint "RES_0603")
      (description "Resistor 0603 5% 0,1W")
      (fields (field (name "MANUFACTURER") "YAGEO") (field (name "TOLERANCE") "5%"))
      (libsource (lib "WB") (part "RES_16k_5p_0603"))
    )
    (comp (ref "R47")
      (value "1k 5%")
      (footprint "RES_0603")
      (description "Resistor 0603 5% 0,1W")
      (fields (field (name "MANUFACTURER") "YAGEO") (field (name "TOLERANCE") "5%"))
      (libsource (lib "WB") (part "RES_1k_5p_0603"))
    )
    (comp (ref "R48")
      (value "10k 5%")
      (footprint "RES_0603")
      (description "Resistor 0603 5% 0,1W")
      (fields (field (name "TOLERANCE") "5%") (field (name "VOLTAGE") "50"))
      (libsource (lib "WB") (part "RES_10k_5p_0603"))
    )
    (comp (ref "R49")
      (value "1k 5%")
      (footprint "RES_0603")
      (description "Resistor 0603 5% 0,1W")
      (fields (field (name "MANUFACTURER") "YAGEO") (field (name "TOLERANCE") "5%"))
      (libsource (lib "WB") (part "RES_1k_5p_0603"))
    )
    (comp (ref "R50")
      (value "dnp")
      (footprint "RES_0603")
      (description "Resistor 0603 5% 0,1W")
      (fields (field (name "TOLERANCE") "5%") (field (name "VOLTAGE") "50"))
      (libsource (lib "") (part "RES_10k_5p_0603_2"))
    )
    (comp (ref "R51")
      (value "10k 5%")
      (footprint "RES_0603")
      (description "Resistor 0603 5% 0,1W")
      (fields (field (name "TOLERANCE") "5%") (field (name "VOLTAGE") "50"))
      (libsource (lib "") (part "RES_10k_5p_0603_2"))
    )
    (comp (ref "R52")
      (value "1k 5%")
      (footprint "RES_0603")
      (description "Resistor 0603 5% 0,1W")
      (fields (field (name "MANUFACTURER") "YAGEO") (field (name "TOLERANCE") "5%"))
      (libsource (lib "WB") (part "RES_1k_5p_0603"))
    )
    (comp (ref "R53")
      (value "510 5%")
      (footprint "RES_0603")
      (description "Resistor 0603 5% 0,1W")
      (fields (field (name "TOLERANCE") "5%") (field (name "VOLTAGE") "50"))
      (libsource (lib "") (part "RES_510_5p_0603_1"))
    )
    (comp (ref "R54")
      (value "1k 5%")
      (footprint "RES_0603")
      (description "Resistor 0603 5% 0,1W")
      (fields (field (name "MANUFACTURER") "YAGEO") (field (name "TOLERANCE") "5%"))
      (libsource (lib "WB") (part "RES_1k_5p_0603"))
    )
    (comp (ref "R55")
      (value "10k 5%")
      (footprint "RES_0603")
      (description "Resistor 0603 5% 0,1W")
      (fields (field (name "TOLERANCE") "5%") (field (name "VOLTAGE") "50"))
      (libsource (lib "") (part "RES_10k_5p_0603_1"))
    )
    (comp (ref "R56")
      (value "10k")
      (footprint "RES_0603")
      (description "Resistor 0603 5% 0,1W")
      (fields (field (name "MANUFACTURER") "YAGEO") (field (name "TOLERANCE") "5%"))
      (libsource (lib "") (part "RES_16k_5p_0603_3"))
    )
    (comp (ref "R57")
      (value "10k")
      (footprint "RES_0603")
      (description "Resistor 0603 5% 0,1W")
      (fields (field (name "MANUFACTURER") "YAGEO") (field (name "TOLERANCE") "5%"))
      (libsource (lib "") (part "RES_16k_5p_0603_1"))
    )
    (comp (ref "R58")
      (value "10k 5%")
      (footprint "RES_0603")
      (description "Resistor 0603 5% 0,1W")
      (fields (field (name "TOLERANCE") "5%") (field (name "VOLTAGE") "50"))
      (libsource (lib "") (part "RES_10k_5p_0603_1"))
    )
    (comp (ref "R59")
      (value "DNP")
      (footprint "RES_1206")
      (description "Resistor 1206 5% 0,25W")
      (fields
        (field (name "MANUFACTURER") "ROYAL OHM")
        (field (name "MANUFACTURER PART NUMBER") "1206S4J0000T5E")
      )
      (libsource (lib "WB") (part "RES_0R_5p_1206"))
    )
    (comp (ref "R60")
      (value "DNP")
      (footprint "RES_1206")
      (description "Resistor 1206 5% 0,25W")
      (fields
        (field (name "MANUFACTURER") "ROYAL OHM")
        (field (name "MANUFACTURER PART NUMBER") "1206S4J0000T5E")
      )
      (libsource (lib "WB") (part "RES_0R_5p_1206"))
    )
    (comp (ref "RT1")
      (value "10k B=3900K NCP21XV103J03RA")
      (footprint "RES_0805")
      (description "TERMISTOR, NTC, 0805 3900K, permissive current 0.4mA")
      (fields
        (field (name "MANUFACTURER") "MURATA")
        (field (name "MANUFACTURER PART NUMBER") "NCP21XV103J03RA")
      )
      (libsource (lib "WB") (part "REST_10k_5p_0805"))
    )
    (comp (ref "RT2")
      (value "10k B=3900K NCP21XV103J03RA")
      (footprint "RES_0805")
      (description "TERMISTOR, NTC, 0805 3900K, permissive current 0.4mA")
      (fields
        (field (name "MANUFACTURER") "MURATA")
        (field (name "MANUFACTURER PART NUMBER") "NCP21XV103J03RA")
      )
      (libsource (lib "WB") (part "REST_10k_5p_0805"))
    )
    (comp (ref "RT3")
      (value "10k B=3900K NCP21XV103J03RA")
      (footprint "RES_0805")
      (description "TERMISTOR, NTC, 0805 3900K, permissive current 0.4mA")
      (fields
        (field (name "MANUFACTURER") "MURATA")
        (field (name "MANUFACTURER PART NUMBER") "NCP21XV103J03RA")
      )
      (libsource (lib "WB") (part "REST_10k_5p_0805"))
    )
    (comp (ref "RV1")
      (value "50VAC 1kA")
      (footprint "RES_VAR_S14")
      (description "warystor S14 30VAC 38VDC 1kA 9J@2ms")
      (fields (field (name "MANUFACTURER") "EPCOS") (field (name "TOLERANCE") "10%"))
      (libsource (lib "WB") (part "RESV_38V_1kA_THT"))
    )
    (comp (ref "T1")
      (value "IPD034N06N3GATMA1")
      (footprint "DPAK_369C_issueD")
      (description "60V N-Mosfet 100A 60V 3.54mohm")
      (fields (field (name "MANUFACTURER") "INFINEON"))
      (libsource (lib "WB") (part "T_IPD034N06N3"))
    )
    (comp (ref "T2")
      (value "IPD034N06N3GATMA1")
      (footprint "DPAK_369C_issueD")
      (description "60V N-Mosfet 100A 60V 3.54mohm")
      (fields (field (name "MANUFACTURER") "INFINEON"))
      (libsource (lib "WB") (part "T_IPD034N06N3"))
    )
    (comp (ref "T3")
      (value "IPD034N06N3GATMA1")
      (footprint "DPAK_369C_issueD")
      (description "60V N-Mosfet 100A 60V 3.54mohm")
      (fields (field (name "MANUFACTURER") "INFINEON"))
      (libsource (lib "WB") (part "T_IPD034N06N3"))
    )
    (comp (ref "T4")
      (value "IPD034N06N3GATMA1")
      (footprint "DPAK_369C_issueD")
      (description "60V N-Mosfet 100A 60V 3.54mohm")
      (fields (field (name "MANUFACTURER") "INFINEON"))
      (libsource (lib "WB") (part "T_IPD034N06N3"))
    )
    (comp (ref "T5")
      (value "N mosfet BSS138")
      (footprint "SOT23-3")
      (description "50V 0.3A N mosfet Rdson 6ohm @UGS=4.5V Qg=2.5nC")
      (fields (field (name "MANUFACTURER") "FAIRCHILD") (field (name "MANUFACTURER PART NUMBER") "BSS138"))
      (libsource (lib "WB") (part "T_BSS138"))
    )
    (comp (ref "T6")
      (value "IPD034N06N3GATMA1")
      (footprint "DPAK_369C_issueD")
      (description "60V N-Mosfet 100A 60V 3.54mohm")
      (fields (field (name "MANUFACTURER") "INFINEON"))
      (libsource (lib "WB") (part "T_IPD034N06N3"))
    )
    (comp (ref "T7")
      (value "IPD034N06N3GATMA1")
      (footprint "DPAK_369C_issueD")
      (description "60V N-Mosfet 100A 60V 3.54mohm")
      (fields (field (name "MANUFACTURER") "INFINEON"))
      (libsource (lib "WB") (part "T_IPD034N06N3"))
    )
    (comp (ref "T8")
      (value "N mosfet BSS138")
      (footprint "SOT23-3")
      (description "50V 0.3A N mosfet Rdson 6ohm @UGS=4.5V Qg=2.5nC")
      (fields (field (name "MANUFACTURER") "FAIRCHILD") (field (name "MANUFACTURER PART NUMBER") "BSS138"))
      (libsource (lib "WB") (part "T_BSS138"))
    )
    (comp (ref "T9")
      (value "N mosfet BSS138")
      (footprint "SOT23-3")
      (description "50V 0.3A N mosfet Rdson 6ohm @UGS=4.5V Qg=2.5nC")
      (fields (field (name "MANUFACTURER") "FAIRCHILD") (field (name "MANUFACTURER PART NUMBER") "BSS138"))
      (libsource (lib "WB") (part "T_BSS138"))
    )
    (comp (ref "T10")
      (value "N mosfet BSS138")
      (footprint "SOT23-3")
      (description "50V 0.3A N mosfet Rdson 6ohm @UGS=4.5V Qg=2.5nC")
      (fields (field (name "MANUFACTURER") "FAIRCHILD") (field (name "MANUFACTURER PART NUMBER") "BSS138"))
      (libsource (lib "WB") (part "T_BSS138"))
    )
    (comp (ref "T11")
      (value "HCPL817-300E")
      (footprint "HCPL-817")
      (description "HCPL817-300E\r\n'0' ctr 50-600%\r\nif 20ma ic 30ma vce 70V vr 4v")
      (fields (field (name "MANUFACTURER PART NUMBER") "HCPL-817-36BE"))
      (libsource (lib "WB") (part "T_HCPL817-300E"))
    )
    (comp (ref "U1")
      (value "TPS57160QDGQRQ1")
      (footprint "MSOP10_DQG_S_PDSO_G10")
      (description "116uA quescient current")
      (fields (field (name "MANUFACTURER") "Texas Instruments"))
      (libsource (lib "WB") (part "IC_TPS57160QDGQRQ1"))
    )
    (comp (ref "U2")
      (value "LMV772QMM/NOPB")
      (footprint "MSOP8_3x3_846AD-01")
      (description "LowOffset,LowNoise,RROOperationalAmplifier")
      (fields (field (name "MANUFACTURER") "TI National Semiconductor"))
      (libsource (lib "WB") (part "IC_LMV772QMM"))
    )
    (comp (ref "U3")
      (value "WT8266-S2")
      (footprint "MOD_WT8266-S2")
      (fields (field (name "MANUFACTURER") "xiaoe") (field (name "VOLTAGE") "3.0 - 3.6"))
      (libsource (lib "WB") (part "MOD_WT8266-S2"))
    )
    (comp (ref "U4")
      (value "MCP1825S-3302ED")
      (footprint "sot223")
      (description "LDO=210mV 6V DC max, Iq 120uA, Cout 1u ceramic")
      (fields
        (field (name "MANUFACTURER") "Microchip")
        (field (name "MANUFACTURER PART NUMBER") "MCP1825S-3302E/DB")
      )
      (libsource (lib "WB") (part "IC_MCP1825S-3.3_SOT223"))
    )
    (comp (ref "U5")
      (value "IC_STM32L431RCT6_LQFP64")
      (footprint "LQFP64_10x10")
      (description "LQFP64, 10x10mm")
      (fields
        (field (name "MANUFACTURER") "STMicroelectronics")
        (field (name "MANUFACTURER PART NUMBER") "STM32L431RCT6")
      )
      (libsource (lib "WB") (part "IC_STM32L431RCT6_LQFP64"))
    )
    (comp (ref "X1")
      (value "OSCX_8M_5,0x3,2")
      (footprint "X_5.0X3.2")
      (description "SMD 5,0x3,2mm xtal drive 100uW max; ESR 150 ohm")
      (fields
        (field (name "MANUFACTURER") "Abracon")
        (field (name "MANUFACTURER PART NUMBER") "ABM3-8.000MHZ-D2Y-T")
      )
      (libsource (lib "WB") (part "OSCX_8M_5,0x3,2"))
    )
  )
  (nets
    (net (code "1") (name "+3") (class "Default")
      (node (ref "C24") (pin "1") (pinfunction "1_1") (pintype "passive"))
      (node (ref "C25") (pin "1") (pinfunction "1_1") (pintype "passive"))
      (node (ref "C30") (pin "1") (pinfunction "1_1") (pintype "passive"))
      (node (ref "C31") (pin "1") (pinfunction "1_1") (pintype "passive"))
      (node (ref "C39") (pin "1") (pinfunction "1_1") (pintype "passive"))
      (node (ref "C40") (pin "1") (pinfunction "1_1") (pintype "passive"))
      (node (ref "C41") (pin "1") (pinfunction "1_1") (pintype "passive"))
      (node (ref "C42") (pin "1") (pinfunction "1_1") (pintype "passive"))
      (node (ref "J5") (pin "4") (pinfunction "VDD_4") (pintype "power_in"))
      (node (ref "L3") (pin "1") (pinfunction "1_1") (pintype "passive"))
      (node (ref "R24") (pin "2") (pinfunction "2_2") (pintype "passive"))
      (node (ref "R27") (pin "1") (pinfunction "1_1") (pintype "passive"))
      (node (ref "R29") (pin "1") (pinfunction "1_1") (pintype "passive"))
      (node (ref "R30") (pin "1") (pinfunction "1_1") (pintype "passive"))
      (node (ref "R31") (pin "1") (pinfunction "1_1") (pintype "passive"))
      (node (ref "R32") (pin "1") (pinfunction "1_1") (pintype "passive"))
      (node (ref "R43") (pin "1") (pinfunction "1_1") (pintype "passive"))
      (node (ref "R44") (pin "1") (pinfunction "1_1") (pintype "passive"))
      (node (ref "R45") (pin "1") (pinfunction "1_1") (pintype "passive"))
      (node (ref "R46") (pin "1") (pinfunction "1_1") (pintype "passive"))
      (node (ref "R48") (pin "1") (pinfunction "1_1") (pintype "passive"))
      (node (ref "R50") (pin "1") (pinfunction "1_1") (pintype "passive"))
      (node (ref "R53") (pin "2") (pinfunction "2_2") (pintype "passive"))
      (node (ref "R55") (pin "1") (pinfunction "1_1") (pintype "passive"))
      (node (ref "U3") (pin "1") (pinfunction "VCC_1") (pintype "power_in"))
      (node (ref "U4") (pin "3") (pinfunction "OUT_3") (pintype "power_in"))
      (node (ref "U5") (pin "1") (pinfunction "VBAT/VLCD_1") (pintype "passive"))
      (node (ref "U5") (pin "13") (pinfunction "VDDA/VREF+_13") (pintype "passive"))
      (node (ref "U5") (pin "19") (pinfunction "VDD/PF5_19") (pintype "passive"))
      (node (ref "U5") (pin "32") (pinfunction "VDD_32") (pintype "passive"))
      (node (ref "U5") (pin "48") (pinfunction "VDD/VUSB/VSA/PF7_48") (pintype "passive"))
      (node (ref "U5") (pin "64") (pinfunction "VDD_64") (pintype "passive"))
    )
    (net (code "2") (name "+5") (class "Default")
      (node (ref "C26") (pin "1") (pinfunction "1_1") (pintype "passive"))
      (node (ref "C27") (pin "1") (pinfunction "1_1") (pintype "passive"))
      (node (ref "C4") (pin "2") (pinfunction "2_2") (pintype "passive"))
      (node (ref "C5") (pin "2") (pinfunction "2_2") (pintype "passive"))
      (node (ref "C8") (pin "1") (pinfunction "1_1") (pintype "passive"))
      (node (ref "C9") (pin "1") (pinfunction "1_1") (pintype "passive"))
      (node (ref "D3") (pin "1") (pinfunction "A_1") (pintype "passive"))
      (node (ref "D5") (pin "1") (pinfunction "A_1") (pintype "passive"))
      (node (ref "D6") (pin "2") (pinfunction "K_2") (pintype "passive"))
      (node (ref "L1") (pin "2") (pinfunction "2_2") (pintype "passive"))
      (node (ref "L2") (pin "1") (pinfunction "1_1") (pintype "passive"))
      (node (ref "Q1") (pin "2") (pinfunction "S_2") (pintype "passive"))
      (node (ref "R35") (pin "1") (pinfunction "1_1") (pintype "passive"))
      (node (ref "R5") (pin "2") (pinfunction "2_2") (pintype "passive"))
      (node (ref "U4") (pin "1") (pinfunction "VI_1") (pintype "input"))
    )
    (net (code "3") (name "/BAT_SWITCH_OFF") (class "Default")
      (node (ref "T8") (pin "1") (pinfunction "G_1") (pintype "passive"))
      (node (ref "U5") (pin "22") (pinfunction "PA6/SPI1_MISO/TIM1_BKIN/TIM16_CH1/ADC1_IN11_22") (pintype "passive"))
    )
    (net (code "4") (name "/BAT_SWITCH_PWM") (class "Default")
      (node (ref "R39") (pin "2") (pinfunction "2_2") (pintype "passive"))
      (node (ref "T10") (pin "1") (pinfunction "G_1") (pintype "passive"))
      (node (ref "T9") (pin "1") (pinfunction "G_1") (pintype "passive"))
      (node (ref "U5") (pin "21") (pinfunction "PA5/TIM2_CH1/SPI1_SCK/ADC1_IN10/DAC1_OUT2_21") (pintype "passive"))
    )
    (net (code "5") (name "/BAT_VOLTAGE") (class "Default")
      (node (ref "C35") (pin "1") (pinfunction "1_1") (pintype "passive"))
      (node (ref "R37") (pin "1") (pinfunction "1_1") (pintype "passive"))
      (node (ref "R40") (pin "2") (pinfunction "2_2") (pintype "passive"))
      (node (ref "U5") (pin "11") (pinfunction "PC3/ADC1IN4/SPI2_MOSI/LPTIM1_ETR/SAI1_SD_A/LPTIM2_ETR_11") (pintype "passive"))
    )
    (net (code "6") (name "/C1") (class "Default")
      (node (ref "K1") (pin "1") (pinfunction "1_1") (pintype "passive"))
      (node (ref "R43") (pin "2") (pinfunction "2_2") (pintype "passive"))
      (node (ref "U5") (pin "25") (pinfunction "PC5/USART3_RX/COMP1_INP/ADC1_IN14/WKUP5_25") (pintype "passive"))
    )
    (net (code "7") (name "/C2") (class "Default")
      (node (ref "K1") (pin "2") (pinfunction "2_2") (pintype "passive"))
      (node (ref "R44") (pin "2") (pinfunction "2_2") (pintype "passive"))
      (node (ref "U5") (pin "27") (pinfunction "COMP1_INM/ADC1_IN16/LPTIM2_IN1/TIM1_CH3N/PB1/VREF+_27") (pintype "passive"))
    )
    (net (code "8") (name "/C3") (class "Default")
      (node (ref "K1") (pin "4") (pinfunction "4_4") (pintype "passive"))
      (node (ref "R45") (pin "2") (pinfunction "2_2") (pintype "passive"))
      (node (ref "U5") (pin "24") (pinfunction "PC4/USART3_TX/COMP1_INM/ADC1_IN13_24") (pintype "passive"))
    )
    (net (code "9") (name "/C4") (class "Default")
      (node (ref "K1") (pin "8") (pinfunction "8_8") (pintype "passive"))
      (node (ref "R46") (pin "2") (pinfunction "2_2") (pintype "passive"))
      (node (ref "U5") (pin "26") (pinfunction "ADC1_IN15/COMP1_OUT/TIM1_CH2N/SPI1_NSS/PB0_26") (pintype "passive"))
    )
    (net (code "10") (name "/ESP_RX") (class "Default")
      (node (ref "U3") (pin "11") (pinfunction "U0TXD/IO1_11") (pintype "bidirectional"))
      (node (ref "U5") (pin "30") (pinfunction "COMP2_OUT/LPUART1_TX/USART3_RX/I2C2_SDA/TIM2_CH4/PB11/VCAP1_30") (pintype "passive"))
    )
    (net (code "11") (name "/ESP_TX") (class "Default")
      (node (ref "U3") (pin "9") (pinfunction "U0RXD/IO3_9") (pintype "bidirectional"))
      (node (ref "U5") (pin "29") (pinfunction "LPUART1_RX/USART3_TX/SPI2_SCK/I2C2_SCL/TIM2_CH3/PB10_29") (pintype "passive"))
    )
    (net (code "12") (name "/EXT_IN") (class "Default")
      (node (ref "R58") (pin "1") (pinfunction "1_1") (pintype "passive"))
      (node (ref "R60") (pin "1") (pinfunction "1_1") (pintype "passive"))
      (node (ref "T11") (pin "3") (pinfunction "E_3") (pintype "passive"))
      (node (ref "U5") (pin "17") (pinfunction "PA3/SAR_VREF+/TIM2_CH4/ADC1IN8/COMP2_INP_17") (pintype "passive"))
    )
    (net (code "13") (name "/INV_CURRENT") (class "Default")
      (node (ref "C22") (pin "1") (pinfunction "1_1") (pintype "passive"))
      (node (ref "R19") (pin "2") (pinfunction "2_2") (pintype "passive"))
      (node (ref "U5") (pin "8") (pinfunction "PC0/ADC1IN1/LPUART1RX/LPTIM1_IN1/I2C3_SCL/LPTIM2_IN1_8") (pintype "passive"))
    )
    (net (code "14") (name "/INV_SWITCH") (class "Default")
      (node (ref "R16") (pin "2") (pinfunction "2_2") (pintype "passive"))
      (node (ref "R17") (pin "1") (pinfunction "1_1") (pintype "passive"))
      (node (ref "R28") (pin "1") (pinfunction "1_1") (pintype "passive"))
      (node (ref "T1") (pin "1") (pinfunction "G_1") (pintype "passive"))
      (node (ref "T2") (pin "1") (pinfunction "G_1") (pintype "passive"))
    )
    (net (code "15") (name "/INV_SWITCH_DRV") (class "Default")
      (node (ref "T5") (pin "1") (pinfunction "G_1") (pintype "passive"))
      (node (ref "U5") (pin "23") (pinfunction "PA7/TIM1_CH1N/I2C3_SCL/SPI1_MOSI/COMP2_OUT/ADC1_IN12_23") (pintype "passive"))
    )
    (net (code "16") (name "/LED_1") (class "Default")
      (node (ref "R47") (pin "2") (pinfunction "2_2") (pintype "passive"))
      (node (ref "U5") (pin "36") (pinfunction "TIM15_CH2/SPI2_MOSI/TIM1_CH3N/RTC_REFIN/PB15_36") (pintype "passive"))
    )
    (net (code "17") (name "/LED_2") (class "Default")
      (node (ref "R49") (pin "2") (pinfunction "2_2") (pintype "passive"))
      (node (ref "U5") (pin "35") (pinfunction "TIM15_CH1/SWPMI1_RX/SPI2_MISO/I2C2_SDA/TIM1_CH2N/PB14_35") (pintype "passive"))
    )
    (net (code "18") (name "/LED_3") (class "Default")
      (node (ref "R52") (pin "2") (pinfunction "2_2") (pintype "passive"))
      (node (ref "U5") (pin "34") (pinfunction "SWPMI1_TX/TIM15_CH1N/SPI2_SCK/I2C2_SCL/TIM1_CH1N/PB13_34") (pintype "passive"))
    )
    (net (code "19") (name "/LED_4") (class "Default")
      (node (ref "R54") (pin "2") (pinfunction "2_2") (pintype "passive"))
      (node (ref "U5") (pin "33") (pinfunction "TIM15_BKIN/SPI2_NSS/I2C2_SMBA/TIM1_BKIN/PB12/SD_VREF+_33") (pintype "passive"))
    )
    (net (code "20") (name "/NRST") (class "Default")
      (node (ref "C38") (pin "1") (pinfunction "1_1") (pintype "passive"))
      (node (ref "J6") (pin "5") (pinfunction "5_5") (pintype "passive"))
      (node (ref "R48") (pin "2") (pinfunction "2_2") (pintype "passive"))
      (node (ref "U5") (pin "7") (pinfunction "NRST_7") (pintype "passive"))
    )
    (net (code "21") (name "/NTC1") (class "Default")
      (node (ref "R32") (pin "2") (pinfunction "2_2") (pintype "passive"))
      (node (ref "RT3") (pin "1") (pinfunction "1_1") (pintype "passive"))
      (node (ref "U5") (pin "14") (pinfunction "PA0/ADC1IN5/TIM2_CH1/COMP1_OUT/OPAMP1_VINP/WKUP1_14") (pintype "passive"))
    )
    (net (code "22") (name "/NTC2") (class "Default")
      (node (ref "R30") (pin "2") (pinfunction "2_2") (pintype "passive"))
      (node (ref "RT1") (pin "1") (pinfunction "1_1") (pintype "passive"))
      (node (ref "U5") (pin "15") (pinfunction "PA1/ADC1IN6/TIM2_CH2/SPI1_SCK/I2C1_SMBA/SPI1_SCK_15") (pintype "passive"))
    )
    (net (code "23") (name "/NTC3") (class "Default")
      (node (ref "R31") (pin "2") (pinfunction "2_2") (pintype "passive"))
      (node (ref "RT2") (pin "1") (pinfunction "1_1") (pintype "passive"))
      (node (ref "U5") (pin "16") (pinfunction "PA2/ADC1IN7/TIM2_CH3/U2_TX/WKUP4/TIM15_CH1/LPUART1_TX_16") (pintype "passive"))
    )
    (net (code "24") (name "/PV_CURRENT") (class "Default")
      (node (ref "C23") (pin "1") (pinfunction "1_1") (pintype "passive"))
      (node (ref "R20") (pin "2") (pinfunction "2_2") (pintype "passive"))
      (node (ref "U5") (pin "9") (pinfunction "PC1/ADC1IN2/LPUART1TX/LPTIM1_OUT/I2C3_SDA_9") (pintype "passive"))
    )
    (net (code "25") (name "/PV_VOLTAGE") (class "Default")
      (node (ref "C12") (pin "1") (pinfunction "1_1") (pintype "passive"))
      (node (ref "R14") (pin "2") (pinfunction "2_2") (pintype "passive"))
      (node (ref "R6") (pin "1") (pinfunction "1_1") (pintype "passive"))
      (node (ref "U5") (pin "10") (pinfunction "PC2/ADC1IN3/SPI2_MISO/LPTIM1_IN2_10") (pintype "passive"))
    )
    (net (code "26") (name "/SD_CMD") (class "Default")
      (node (ref "J5") (pin "3") (pinfunction "CMD_3") (pintype "input"))
      (node (ref "U5") (pin "54") (pinfunction "SDMMC1_CMD/TSC_SYNC/PD2_54") (pintype "passive"))
    )
    (net (code "27") (name "/SWDCLK") (class "Default")
      (node (ref "J6") (pin "2") (pinfunction "2_2") (pintype "passive"))
      (node (ref "U5") (pin "49") (pinfunction "PA14/JTCK-SWCLK/LPTIM1_OUT/I2C1_SMBA_49") (pintype "passive"))
    )
    (net (code "28") (name "/SWDIO") (class "Default")
      (node (ref "J6") (pin "4") (pinfunction "4_4") (pintype "passive"))
      (node (ref "U5") (pin "46") (pinfunction "PA13/JTMS-SWDIO/IR_OUT/SWPMI1_TX_46") (pintype "passive"))
    )
    (net (code "29") (name "/TRACE_SWO") (class "Default")
      (node (ref "J6") (pin "6") (pinfunction "6_6") (pintype "passive"))
      (node (ref "U5") (pin "55") (pinfunction "SPI1_SCK/TIM2_CH2/JTDO-TRACESWO/PB3_55") (pintype "passive"))
    )
    (net (code "30") (name "/V_GATE") (class "Default")
      (node (ref "C33") (pin "1") (pinfunction "1_1") (pintype "passive"))
      (node (ref "D7") (pin "2") (pinfunction "K_2") (pintype "passive"))
      (node (ref "R33") (pin "1") (pinfunction "1_1") (pintype "passive"))
      (node (ref "R34") (pin "2") (pinfunction "2_2") (pintype "passive"))
      (node (ref "T3") (pin "1") (pinfunction "G_1") (pintype "passive"))
      (node (ref "T4") (pin "1") (pinfunction "G_1") (pintype "passive"))
      (node (ref "T6") (pin "1") (pinfunction "G_1") (pintype "passive"))
      (node (ref "T7") (pin "1") (pinfunction "G_1") (pintype "passive"))
    )
    (net (code "31") (name "/V_SOURCE") (class "Default")
      (node (ref "C28") (pin "2") (pinfunction "2_2") (pintype "passive"))
      (node (ref "C29") (pin "1") (pinfunction "1_1") (pintype "passive"))
      (node (ref "C33") (pin "2") (pinfunction "2_2") (pintype "passive"))
      (node (ref "R25") (pin "2") (pinfunction "2_2") (pintype "passive"))
      (node (ref "R26") (pin "1") (pinfunction "1_1") (pintype "passive"))
      (node (ref "R34") (pin "1") (pinfunction "1_1") (pintype "passive"))
      (node (ref "R36") (pin "1") (pinfunction "1_1") (pintype "passive"))
      (node (ref "T3") (pin "3") (pinfunction "S_3") (pintype "passive"))
      (node (ref "T4") (pin "3") (pinfunction "S_3") (pintype "passive"))
      (node (ref "T6") (pin "3") (pinfunction "S_3") (pintype "passive"))
      (node (ref "T7") (pin "3") (pinfunction "S_3") (pintype "passive"))
    )
    (net (code "32") (name "/rx") (class "Default")
      (node (ref "J4") (pin "2") (pinfunction "2_2") (pintype "passive"))
      (node (ref "R42") (pin "1") (pinfunction "1_1") (pintype "passive"))
    )
    (net (code "33") (name "/tx") (class "Default")
      (node (ref "J4") (pin "1") (pinfunction "1_1") (pintype "passive"))
      (node (ref "R41") (pin "1") (pinfunction "1_1") (pintype "passive"))
    )
    (net (code "34") (name "GND") (class "Default")
      (node (ref "C10") (pin "2") (pinfunction "2_2") (pintype "passive"))
      (node (ref "C11") (pin "1") (pinfunction "1_1") (pintype "passive"))
      (node (ref "C12") (pin "2") (pinfunction "2_2") (pintype "passive"))
      (node (ref "C13") (pin "2") (pinfunction "2_2") (pintype "passive"))
      (node (ref "C14") (pin "2") (pinfunction "2_2") (pintype "passive"))
      (node (ref "C17") (pin "2") (pinfunction "2_2") (pintype "passive"))
      (node (ref "C18") (pin "2") (pinfunction "2_2") (pintype "passive"))
      (node (ref "C19") (pin "2") (pinfunction "2_2") (pintype "passive"))
      (node (ref "C2") (pin "1") (pinfunction "1_1") (pintype "passive"))
      (node (ref "C20") (pin "2") (pinfunction "2_2") (pintype "passive"))
      (node (ref "C21") (pin "2") (pinfunction "2_2") (pintype "passive"))
      (node (ref "C22") (pin "2") (pinfunction "2_2") (pintype "passive"))
      (node (ref "C23") (pin "2") (pinfunction "2_2") (pintype "passive"))
      (node (ref "C24") (pin "2") (pinfunction "2_2") (pintype "passive"))
      (node (ref "C25") (pin "2") (pinfunction "2_2") (pintype "passive"))
      (node (ref "C26") (pin "2") (pinfunction "2_2") (pintype "passive"))
      (node (ref "C27") (pin "2") (pinfunction "2_2") (pintype "passive"))
      (node (ref "C3") (pin "1") (pinfunction "1_1") (pintype "passive"))
      (node (ref "C30") (pin "2") (pinfunction "2_2") (pintype "passive"))
      (node (ref "C31") (pin "2") (pinfunction "2_2") (pintype "passive"))
      (node (ref "C32") (pin "2") (pinfunction "2_2") (pintype "passive"))
      (node (ref "C35") (pin "2") (pinfunction "2_2") (pintype "passive"))
      (node (ref "C36") (pin "1") (pinfunction "1_1") (pintype "passive"))
      (node (ref "C37") (pin "1") (pinfunction "1_1") (pintype "passive"))
      (node (ref "C38") (pin "2") (pinfunction "2_2") (pintype "passive"))
      (node (ref "C39") (pin "2") (pinfunction "2_2") (pintype "passive"))
      (node (ref "C4") (pin "1") (pinfunction "1_1") (pintype "passive"))
      (node (ref "C40") (pin "2") (pinfunction "2_2") (pintype "passive"))
      (node (ref "C41") (pin "2") (pinfunction "2_2") (pintype "passive"))
      (node (ref "C42") (pin "2") (pinfunction "2_2") (pintype "passive"))
      (node (ref "C5") (pin "1") (pinfunction "1_1") (pintype "passive"))
      (node (ref "C7") (pin "2") (pinfunction "2_2") (pintype "passive"))
      (node (ref "C8") (pin "2") (pinfunction "2_2") (pintype "passive"))
      (node (ref "C9") (pin "2") (pinfunction "2_2") (pintype "passive"))
      (node (ref "D10") (pin "2") (pinfunction "K_2") (pintype "passive"))
      (node (ref "D11") (pin "2") (pinfunction "K_2") (pintype "passive"))
      (node (ref "D12") (pin "2") (pinfunction "K_2") (pintype "passive"))
      (node (ref "D13") (pin "2") (pinfunction "K_2") (pintype "passive"))
      (node (ref "D4") (pin "1") (pinfunction "A_1") (pintype "passive"))
      (node (ref "J2") (pin "2") (pinfunction "2_2") (pintype "passive"))
      (node (ref "J4") (pin "3") (pinfunction "3_3") (pintype "passive"))
      (node (ref "J5") (pin "6") (pinfunction "GND_6") (pintype "power_in"))
      (node (ref "J6") (pin "3") (pinfunction "3_3") (pintype "passive"))
      (node (ref "K1") (pin "C") (pinfunction "C_C") (pintype "passive"))
      (node (ref "R11") (pin "2") (pinfunction "2_2") (pintype "passive"))
      (node (ref "R12") (pin "1") (pinfunction "1_1") (pintype "passive"))
      (node (ref "R13") (pin "1") (pinfunction "1_1") (pintype "passive"))
      (node (ref "R14") (pin "1") (pinfunction "1_1") (pintype "passive"))
      (node (ref "R15") (pin "1") (pinfunction "1_1") (pintype "passive"))
      (node (ref "R21") (pin "1") (pinfunction "1_1") (pintype "passive"))
      (node (ref "R3") (pin "2") (pinfunction "2_2") (pintype "passive"))
      (node (ref "R39") (pin "1") (pinfunction "1_1") (pintype "passive"))
      (node (ref "R40") (pin "1") (pinfunction "1_1") (pintype "passive"))
      (node (ref "R51") (pin "1") (pinfunction "1_1") (pintype "passive"))
      (node (ref "R58") (pin "2") (pinfunction "2_2") (pintype "passive"))
      (node (ref "R7") (pin "1") (pinfunction "1_1") (pintype "passive"))
      (node (ref "RT1") (pin "2") (pinfunction "2_2") (pintype "passive"))
      (node (ref "RT2") (pin "2") (pinfunction "2_2") (pintype "passive"))
      (node (ref "RT3") (pin "2") (pinfunction "2_2") (pintype "passive"))
      (node (ref "T10") (pin "2") (pinfunction "S_2") (pintype "passive"))
      (node (ref "T5") (pin "2") (pinfunction "S_2") (pintype "passive"))
      (node (ref "T8") (pin "2") (pinfunction "S_2") (pintype "passive"))
      (node (ref "T9") (pin "2") (pinfunction "S_2") (pintype "passive"))
      (node (ref "U1") (pin "11") (pinfunction "ETPAD_11") (pintype "passive"))
      (node (ref "U1") (pin "9") (pinfunction "GND_9") (pintype "passive"))
      (node (ref "U2") (pin "4") (pinfunction "-V_4") (pintype "power_in"))
      (node (ref "U3") (pin "10") (pinfunction "GND_10") (pintype "power_in"))
      (node (ref "U3") (pin "18") (pinfunction "GND_18") (pintype "power_in"))
      (node (ref "U3") (pin "6") (pinfunction "GND_6") (pintype "power_in"))
      (node (ref "U4") (pin "2") (pinfunction "ADJ/GN_2") (pintype "power_in"))
      (node (ref "U4") (pin "4") (pintype "power_in"))
      (node (ref "U5") (pin "12") (pinfunction "VSSA_12") (pintype "passive"))
      (node (ref "U5") (pin "18") (pinfunction "VSS/PF4/PA3_18") (pintype "passive"))
      (node (ref "U5") (pin "31") (pinfunction "VSS/VCAP1_31") (pintype "passive"))
      (node (ref "U5") (pin "47") (pinfunction "VSS/VCAP2/PF6_47") (pintype "passive"))
      (node (ref "U5") (pin "63") (pinfunction "VSS_63") (pintype "passive"))
    )
    (net (code "35") (name "Net-(C17-Pad1)") (class "Default")
      (node (ref "C17") (pin "1") (pinfunction "1_1") (pintype "passive"))
      (node (ref "R18") (pin "1") (pinfunction "1_1") (pintype "passive"))
    )
    (net (code "36") (name "Net-(D1-A)") (class "Default")
      (node (ref "C29") (pin "2") (pinfunction "2_2") (pintype "passive"))
      (node (ref "D1") (pin "1") (pinfunction "A_1") (pintype "passive"))
      (node (ref "J1") (pin "1") (pinfunction "1_1") (pintype "passive"))
      (node (ref "J2") (pin "1") (pinfunction "1_1") (pintype "passive"))
      (node (ref "R16") (pin "1") (pinfunction "1_1") (pintype "passive"))
      (node (ref "R26") (pin "2") (pinfunction "2_2") (pintype "passive"))
      (node (ref "R6") (pin "2") (pinfunction "2_2") (pintype "passive"))
      (node (ref "RV1") (pin "2") (pinfunction "2_2") (pintype "passive"))
      (node (ref "T4") (pin "4") (pinfunction "D_4") (pintype "passive"))
      (node (ref "T7") (pin "4") (pinfunction "D_4") (pintype "passive"))
    )
    (net (code "37") (name "Net-(D2-K)") (class "Default")
      (node (ref "D2") (pin "2") (pinfunction "K_2") (pintype "passive"))
      (node (ref "R12") (pin "2") (pinfunction "2_2") (pintype "passive"))
    )
    (net (code "38") (name "Net-(D3-K)") (class "Default")
      (node (ref "D3") (pin "2") (pinfunction "K_2") (pintype "passive"))
      (node (ref "R15") (pin "2") (pinfunction "2_2") (pintype "passive"))
    )
    (net (code "39") (name "Net-(D4-K)") (class "Default")
      (node (ref "C6") (pin "2") (pinfunction "2_2") (pintype "passive"))
      (node (ref "D4") (pin "2") (pinfunction "K_2") (pintype "passive"))
      (node (ref "L1") (pin "1") (pinfunction "1_1") (pintype "passive"))
      (node (ref "U1") (pin "10") (pinfunction "PH_10") (pintype "passive"))
    )
    (net (code "40") (name "Net-(D5-K)") (class "Default")
      (node (ref "D5") (pin "2") (pinfunction "K_2") (pintype "passive"))
      (node (ref "D6") (pin "1") (pinfunction "A_1") (pintype "passive"))
    )
    (net (code "41") (name "Net-(D7-A)") (class "Default")
      (node (ref "C34") (pin "1") (pinfunction "1_1") (pintype "passive"))
      (node (ref "D7") (pin "1") (pinfunction "A_1") (pintype "passive"))
      (node (ref "D8") (pin "2") (pinfunction "K_2") (pintype "passive"))
    )
    (net (code "42") (name "Net-(D8-A)") (class "Default")
      (node (ref "D8") (pin "1") (pinfunction "A_1") (pintype "passive"))
      (node (ref "Q1") (pin "3") (pinfunction "D_3") (pintype "passive"))
    )
    (net (code "43") (name "Net-(D9-A)") (class "Default")
      (node (ref "C28") (pin "1") (pinfunction "1_1") (pintype "passive"))
      (node (ref "D9") (pin "1") (pinfunction "A_1") (pintype "passive"))
      (node (ref "J3") (pin "1") (pinfunction "1_1") (pintype "passive"))
      (node (ref "R25") (pin "1") (pinfunction "1_1") (pintype "passive"))
      (node (ref "R37") (pin "2") (pinfunction "2_2") (pintype "passive"))
      (node (ref "T3") (pin "4") (pinfunction "D_4") (pintype "passive"))
      (node (ref "T6") (pin "4") (pinfunction "D_4") (pintype "passive"))
    )
    (net (code "44") (name "Net-(D10-A)") (class "Default")
      (node (ref "D10") (pin "1") (pinfunction "A_1") (pintype "passive"))
      (node (ref "R47") (pin "1") (pinfunction "1_1") (pintype "passive"))
    )
    (net (code "45") (name "Net-(D11-A)") (class "Default")
      (node (ref "D11") (pin "1") (pinfunction "A_1") (pintype "passive"))
      (node (ref "R49") (pin "1") (pinfunction "1_1") (pintype "passive"))
    )
    (net (code "46") (name "Net-(D12-A)") (class "Default")
      (node (ref "D12") (pin "1") (pinfunction "A_1") (pintype "passive"))
      (node (ref "R52") (pin "1") (pinfunction "1_1") (pintype "passive"))
    )
    (net (code "47") (name "Net-(D13-A)") (class "Default")
      (node (ref "D13") (pin "1") (pinfunction "A_1") (pintype "passive"))
      (node (ref "R54") (pin "1") (pinfunction "1_1") (pintype "passive"))
    )
    (net (code "48") (name "Net-(D14-A)") (class "Default")
      (node (ref "D14") (pin "1") (pinfunction "A_1") (pintype "passive"))
      (node (ref "J7") (pin "2") (pinfunction "2_2") (pintype "passive"))
      (node (ref "R57") (pin "2") (pinfunction "2_2") (pintype "passive"))
      (node (ref "R60") (pin "2") (pinfunction "2_2") (pintype "passive"))
      (node (ref "T11") (pin "2") (pinfunction "K_2") (pintype "passive"))
    )
    (net (code "49") (name "Net-(D14-K)") (class "Default")
      (node (ref "D14") (pin "2") (pinfunction "K_2") (pintype "passive"))
      (node (ref "R56") (pin "2") (pinfunction "2_2") (pintype "passive"))
      (node (ref "R57") (pin "1") (pinfunction "1_1") (pintype "passive"))
      (node (ref "R59") (pin "2") (pinfunction "2_2") (pintype "passive"))
      (node (ref "T11") (pin "1") (pinfunction "A_1") (pintype "passive"))
    )
    (net (code "50") (name "Net-(J3-Pad2)") (class "Default")
      (node (ref "J3") (pin "2") (pinfunction "2_2") (pintype "passive"))
      (node (ref "R10") (pin "2") (pinfunction "2_2") (pintype "passive"))
      (node (ref "R2") (pin "2") (pinfunction "2_2") (pintype "passive"))
      (node (ref "R3") (pin "1") (pinfunction "1_1") (pintype "passive"))
      (node (ref "R9") (pin "2") (pinfunction "2_2") (pintype "passive"))
      (node (ref "RV1") (pin "1") (pinfunction "1_1") (pintype "passive"))
    )
    (net (code "51") (name "Net-(J5-CLK)") (class "Default")
      (node (ref "J5") (pin "5") (pinfunction "CLK_5") (pintype "input"))
      (node (ref "U5") (pin "53") (pinfunction "SDMMC1_CK/USART3_CK/SPI3_MOSI/PC12_53") (pintype "passive"))
    )
    (net (code "52") (name "Net-(J5-DAT0)") (class "Default")
      (node (ref "J5") (pin "7") (pinfunction "DAT0_7") (pintype "bidirectional"))
      (node (ref "U5") (pin "39") (pinfunction "SDMMC1_D0/TSC_G4_IO3/PC8_39") (pintype "passive"))
    )
    (net (code "53") (name "Net-(J5-DAT1)") (class "Default")
      (node (ref "J5") (pin "8") (pinfunction "DAT1_8") (pintype "bidirectional"))
      (node (ref "U5") (pin "40") (pinfunction "SDMMC1_D1/TSC_G4_IO4/PC9_40") (pintype "passive"))
    )
    (net (code "54") (name "Net-(J5-DAT2)") (class "Default")
      (node (ref "J5") (pin "1") (pinfunction "DAT2_1") (pintype "bidirectional"))
      (node (ref "U5") (pin "51") (pinfunction "SDMMC1_D2/USART3_TX/SPI3_SCK/PC10_51") (pintype "passive"))
    )
    (net (code "55") (name "Net-(J5-DAT3{slash}CD)") (class "Default")
      (node (ref "J5") (pin "2") (pinfunction "DAT3/CD_2") (pintype "bidirectional"))
      (node (ref "U5") (pin "52") (pinfunction "SDMMC1_D3/USART3_RX/SPI3_MISO/PC11_52") (pintype "passive"))
    )
    (net (code "56") (name "Net-(J6-Pad1)") (class "Default")
      (node (ref "J6") (pin "1") (pinfunction "1_1") (pintype "passive"))
      (node (ref "R53") (pin "1") (pinfunction "1_1") (pintype "passive"))
    )
    (net (code "57") (name "Net-(J7-Pad1)") (class "Default")
      (node (ref "J7") (pin "1") (pinfunction "1_1") (pintype "passive"))
      (node (ref "R56") (pin "1") (pinfunction "1_1") (pintype "passive"))
    )
    (net (code "58") (name "Net-(Q1-G)") (class "Default")
      (node (ref "Q1") (pin "1") (pinfunction "G_1") (pintype "passive"))
      (node (ref "R35") (pin "2") (pinfunction "2_2") (pintype "passive"))
      (node (ref "R38") (pin "2") (pinfunction "2_2") (pintype "passive"))
    )
    (net (code "59") (name "Net-(T1-D)") (class "Default")
      (node (ref "C1") (pin "1") (pinfunction "1_1") (pintype "passive"))
      (node (ref "J1") (pin "2") (pinfunction "2_2") (pintype "passive"))
      (node (ref "R1") (pin "1") (pinfunction "1_1") (pintype "passive"))
      (node (ref "T1") (pin "4") (pinfunction "D_4") (pintype "passive"))
      (node (ref "T2") (pin "4") (pinfunction "D_4") (pintype "passive"))
    )
    (net (code "60") (name "Net-(T1-S)") (class "Default")
      (node (ref "C1") (pin "2") (pinfunction "2_2") (pintype "passive"))
      (node (ref "R1") (pin "2") (pinfunction "2_2") (pintype "passive"))
      (node (ref "R17") (pin "2") (pinfunction "2_2") (pintype "passive"))
      (node (ref "R2") (pin "1") (pinfunction "1_1") (pintype "passive"))
      (node (ref "R8") (pin "2") (pinfunction "2_2") (pintype "passive"))
      (node (ref "T1") (pin "3") (pinfunction "S_3") (pintype "passive"))
      (node (ref "T2") (pin "3") (pinfunction "S_3") (pintype "passive"))
    )
    (net (code "61") (name "Net-(T5-D)") (class "Default")
      (node (ref "R28") (pin "2") (pinfunction "2_2") (pintype "passive"))
      (node (ref "T5") (pin "3") (pinfunction "D_3") (pintype "passive"))
    )
    (net (code "62") (name "Net-(T8-D)") (class "Default")
      (node (ref "R33") (pin "2") (pinfunction "2_2") (pintype "passive"))
      (node (ref "T8") (pin "3") (pinfunction "D_3") (pintype "passive"))
    )
    (net (code "63") (name "Net-(T9-D)") (class "Default")
      (node (ref "C34") (pin "2") (pinfunction "2_2") (pintype "passive"))
      (node (ref "R36") (pin "2") (pinfunction "2_2") (pintype "passive"))
      (node (ref "T9") (pin "3") (pinfunction "D_3") (pintype "passive"))
    )
    (net (code "64") (name "Net-(T10-D)") (class "Default")
      (node (ref "R38") (pin "1") (pinfunction "1_1") (pintype "passive"))
      (node (ref "T10") (pin "3") (pinfunction "D_3") (pintype "passive"))
    )
    (net (code "65") (name "Net-(T11-C)") (class "Default")
      (node (ref "R55") (pin "2") (pinfunction "2_2") (pintype "passive"))
      (node (ref "R59") (pin "1") (pinfunction "1_1") (pintype "passive"))
      (node (ref "T11") (pin "4") (pinfunction "C_4") (pintype "passive"))
    )
    (net (code "66") (name "Net-(U1-BOOT)") (class "Default")
      (node (ref "C6") (pin "1") (pinfunction "1_1") (pintype "passive"))
      (node (ref "U1") (pin "1") (pinfunction "BOOT_1") (pintype "passive"))
    )
    (net (code "67") (name "Net-(U1-COMP)") (class "Default")
      (node (ref "C13") (pin "1") (pinfunction "1_1") (pintype "passive"))
      (node (ref "R18") (pin "2") (pinfunction "2_2") (pintype "passive"))
      (node (ref "U1") (pin "8") (pinfunction "COMP_8") (pintype "passive"))
    )
    (net (code "68") (name "Net-(U1-EN)") (class "Default")
      (node (ref "C7") (pin "1") (pinfunction "1_1") (pintype "passive"))
      (node (ref "R4") (pin "1") (pinfunction "1_1") (pintype "passive"))
      (node (ref "R7") (pin "2") (pinfunction "2_2") (pintype "passive"))
      (node (ref "U1") (pin "3") (pinfunction "EN_3") (pintype "passive"))
    )
    (net (code "69") (name "Net-(U1-RT{slash}CLK)") (class "Default")
      (node (ref "R21") (pin "2") (pinfunction "2_2") (pintype "passive"))
      (node (ref "U1") (pin "5") (pinfunction "RT/CLK_5") (pintype "passive"))
    )
    (net (code "70") (name "Net-(U1-SS{slash}TR)") (class "Default")
      (node (ref "C14") (pin "1") (pinfunction "1_1") (pintype "passive"))
      (node (ref "U1") (pin "4") (pinfunction "SS/TR_4") (pintype "passive"))
    )
    (net (code "71") (name "Net-(U1-VSENSE)") (class "Default")
      (node (ref "R13") (pin "2") (pinfunction "2_2") (pintype "passive"))
      (node (ref "R5") (pin "1") (pinfunction "1_1") (pintype "passive"))
      (node (ref "U1") (pin "7") (pinfunction "VSENSE_7") (pintype "passive"))
    )
    (net (code "72") (name "Net-(U2A-+)") (class "Default")
      (node (ref "C16") (pin "2") (pinfunction "2_2") (pintype "passive"))
      (node (ref "C21") (pin "1") (pinfunction "1_1") (pintype "passive"))
      (node (ref "R10") (pin "1") (pinfunction "1_1") (pintype "passive"))
      (node (ref "U2") (pin "3") (pinfunction "+_3") (pintype "input"))
    )
    (net (code "73") (name "Net-(U2A-+V)") (class "Default")
      (node (ref "C10") (pin "1") (pinfunction "1_1") (pintype "passive"))
      (node (ref "C11") (pin "2") (pinfunction "2_2") (pintype "passive"))
      (node (ref "L2") (pin "2") (pinfunction "2_2") (pintype "passive"))
      (node (ref "L3") (pin "2") (pinfunction "2_2") (pintype "passive"))
      (node (ref "U2") (pin "8") (pinfunction "+V_8") (pintype "power_in"))
    )
    (net (code "74") (name "Net-(U2A--)") (class "Default")
      (node (ref "C16") (pin "1") (pinfunction "1_1") (pintype "passive"))
      (node (ref "C19") (pin "1") (pinfunction "1_1") (pintype "passive"))
      (node (ref "R11") (pin "1") (pinfunction "1_1") (pintype "passive"))
      (node (ref "R23") (pin "2") (pinfunction "2_2") (pintype "passive"))
      (node (ref "U2") (pin "2") (pinfunction "-_2") (pintype "input"))
    )
    (net (code "75") (name "Net-(U2A-O)") (class "Default")
      (node (ref "R20") (pin "1") (pinfunction "1_1") (pintype "passive"))
      (node (ref "R23") (pin "1") (pinfunction "1_1") (pintype "passive"))
      (node (ref "U2") (pin "1") (pinfunction "O_1") (pintype "output"))
    )
    (net (code "76") (name "Net-(U2B-+)") (class "Default")
      (node (ref "C15") (pin "2") (pinfunction "2_2") (pintype "passive"))
      (node (ref "C20") (pin "1") (pinfunction "1_1") (pintype "passive"))
      (node (ref "R8") (pin "1") (pinfunction "1_1") (pintype "passive"))
      (node (ref "U2") (pin "5") (pinfunction "+_5") (pintype "input"))
    )
    (net (code "77") (name "Net-(U2B--)") (class "Default")
      (node (ref "C15") (pin "1") (pinfunction "1_1") (pintype "passive"))
      (node (ref "C18") (pin "1") (pinfunction "1_1") (pintype "passive"))
      (node (ref "R22") (pin "2") (pinfunction "2_2") (pintype "passive"))
      (node (ref "R9") (pin "1") (pinfunction "1_1") (pintype "passive"))
      (node (ref "U2") (pin "6") (pinfunction "-_6") (pintype "input"))
    )
    (net (code "78") (name "Net-(U2B-O)") (class "Default")
      (node (ref "R19") (pin "1") (pinfunction "1_1") (pintype "passive"))
      (node (ref "R22") (pin "1") (pinfunction "1_1") (pintype "passive"))
      (node (ref "U2") (pin "7") (pinfunction "O_7") (pintype "output"))
    )
    (net (code "79") (name "Net-(U3-EN{slash}CH_PD)") (class "Default")
      (node (ref "R27") (pin "2") (pinfunction "2_2") (pintype "passive"))
      (node (ref "U3") (pin "14") (pinfunction "EN/CH_PD_14") (pintype "input"))
    )
    (net (code "80") (name "Net-(U3-IO0)") (class "Default")
      (node (ref "R24") (pin "1") (pinfunction "1_1") (pintype "passive"))
      (node (ref "U3") (pin "3") (pinfunction "IO0_3") (pintype "bidirectional"))
    )
    (net (code "81") (name "Net-(U3-RSTB)") (class "Default")
      (node (ref "C32") (pin "1") (pinfunction "1_1") (pintype "passive"))
      (node (ref "R29") (pin "2") (pinfunction "2_2") (pintype "passive"))
      (node (ref "U3") (pin "12") (pinfunction "RSTB_12") (pintype "input"))
    )
    (net (code "82") (name "Net-(U5A-PA9{slash}TIM1_CH2{slash}I2C1_SCL{slash}USART1_TX{slash}TIM15_BKIN)") (class "Default")
      (node (ref "R41") (pin "2") (pinfunction "2_2") (pintype "passive"))
      (node (ref "U5") (pin "42") (pinfunction "PA9/TIM1_CH2/I2C1_SCL/USART1_TX/TIM15_BKIN_42") (pintype "passive"))
    )
    (net (code "83") (name "Net-(U5A-PA10{slash}TIM1_CH3{slash}I2C1_SDA{slash}USART1_RX{slash})") (class "Default")
      (node (ref "R42") (pin "2") (pinfunction "2_2") (pintype "passive"))
      (node (ref "U5") (pin "43") (pinfunction "PA10/TIM1_CH3/I2C1_SDA/USART1_RX/_43") (pintype "passive"))
    )
    (net (code "84") (name "Net-(U5B-BOOT0{slash}PH3)") (class "Default")
      (node (ref "R50") (pin "2") (pinfunction "2_2") (pintype "passive"))
      (node (ref "R51") (pin "2") (pinfunction "2_2") (pintype "passive"))
      (node (ref "U5") (pin "60") (pinfunction "BOOT0/PH3_60") (pintype "passive"))
    )
    (net (code "85") (name "Net-(U5B-PF0{slash}PD0{slash}PH0_-_OSC_IN)") (class "Default")
      (node (ref "C37") (pin "2") (pinfunction "2_2") (pintype "passive"))
      (node (ref "U5") (pin "5") (pinfunction "PF0/PD0/PH0_-_OSC_IN_5") (pintype "passive"))
      (node (ref "X1") (pin "2") (pinfunction "2_2") (pintype "passive"))
    )
    (net (code "86") (name "Net-(U5B-PF1{slash}PD1{slash}PH1_-_OSC_OUT)") (class "Default")
      (node (ref "C36") (pin "2") (pinfunction "2_2") (pintype "passive"))
      (node (ref "U5") (pin "6") (pinfunction "PF1/PD1/PH1_-_OSC_OUT_6") (pintype "passive"))
      (node (ref "X1") (pin "1") (pinfunction "1_1") (pintype "passive"))
    )
    (net (code "87") (name "SMPS") (class "Default")
      (node (ref "C2") (pin "2") (pinfunction "2_2") (pintype "passive"))
      (node (ref "C3") (pin "2") (pinfunction "2_2") (pintype "passive"))
      (node (ref "D1") (pin "2") (pinfunction "K_2") (pintype "passive"))
      (node (ref "D2") (pin "1") (pinfunction "A_1") (pintype "passive"))
      (node (ref "D9") (pin "2") (pinfunction "K_2") (pintype "passive"))
      (node (ref "R4") (pin "2") (pinfunction "2_2") (pintype "passive"))
      (node (ref "U1") (pin "2") (pinfunction "VIN_2") (pintype "passive"))
    )
    (net (code "88") (name "unconnected-(U1-PWRGD-Pad6)") (class "Default")
      (node (ref "U1") (pin "6") (pinfunction "PWRGD_6") (pintype "passive"))
    )
    (net (code "89") (name "unconnected-(U3-IO2{slash}U1TXD{slash}SDA-Pad4)") (class "Default")
      (node (ref "U3") (pin "4") (pinfunction "IO2/U1TXD/SDA_4") (pintype "bidirectional"))
    )
    (net (code "90") (name "unconnected-(U3-IO4-Pad2)") (class "Default")
      (node (ref "U3") (pin "2") (pinfunction "IO4_2") (pintype "bidirectional"))
    )
    (net (code "91") (name "unconnected-(U3-IO5-Pad8)") (class "Default")
      (node (ref "U3") (pin "8") (pinfunction "IO5_8") (pintype "bidirectional"))
    )
    (net (code "92") (name "unconnected-(U3-IO12{slash}MISO{slash}PWM0-Pad16)") (class "Default")
      (node (ref "U3") (pin "16") (pinfunction "IO12/MISO/PWM0_16") (pintype "bidirectional"))
    )
    (net (code "93") (name "unconnected-(U3-IO13{slash}MOSI{slash}-Pad7)") (class "Default")
      (node (ref "U3") (pin "7") (pinfunction "IO13/MOSI/_7") (pintype "bidirectional"))
    )
    (net (code "94") (name "unconnected-(U3-IO14{slash}CLK{slash}SCL{slash}PWM2-Pad17)") (class "Default")
      (node (ref "U3") (pin "17") (pinfunction "IO14/CLK/SCL/PWM2_17") (pintype "bidirectional"))
    )
    (net (code "95") (name "unconnected-(U3-IO15{slash}MIDO{slash}U0RTS{slash}PWM1-Pad5)") (class "Default")
      (node (ref "U3") (pin "5") (pinfunction "IO15/MIDO/U0RTS/PWM1_5") (pintype "bidirectional"))
    )
    (net (code "96") (name "unconnected-(U3-IO16{slash}WKUP-Pad15)") (class "Default")
      (node (ref "U3") (pin "15") (pinfunction "IO16/WKUP_15") (pintype "passive"))
    )
    (net (code "97") (name "unconnected-(U3-TOUT-Pad13)") (class "Default")
      (node (ref "U3") (pin "13") (pinfunction "TOUT_13") (pintype "input+no_connect"))
    )
    (net (code "98") (name "unconnected-(U5A-COMP1_INP{slash}I2C3_SMBA{slash}LPTIM1_OUT{slash}RTC_OUT{slash}PB2-Pad28)") (class "Default")
      (node (ref "U5") (pin "28") (pinfunction "COMP1_INP/I2C3_SMBA/LPTIM1_OUT/RTC_OUT/PB2_28") (pintype "passive"))
    )
    (net (code "99") (name "unconnected-(U5A-COMP2_INP{slash}SPI1_MISO{slash}I2C3_SDA{slash}NJTRST{slash}PB4-Pad56)") (class "Default")
      (node (ref "U5") (pin "56") (pinfunction "COMP2_INP/SPI1_MISO/I2C3_SDA/NJTRST/PB4_56") (pintype "passive"))
    )
    (net (code "100") (name "unconnected-(U5A-PA4{slash}SPI1_NSS{slash}ADC1_IN9{slash}LPTIM2_OUT{slash}DAC1_OUT-Pad20)") (class "Default")
      (node (ref "U5") (pin "20") (pinfunction "PA4/SPI1_NSS/ADC1_IN9/LPTIM2_OUT/DAC1_OUT_20") (pintype "passive"))
    )
    (net (code "101") (name "unconnected-(U5A-PA8{slash}TIM1_CH1{slash}SAI1_SCK_A{slash}LPTIM2_OUT{slash}USART1_CK-Pad41)") (class "Default")
      (node (ref "U5") (pin "41") (pinfunction "PA8/TIM1_CH1/SAI1_SCK_A/LPTIM2_OUT/USART1_CK_41") (pintype "passive"))
    )
    (net (code "102") (name "unconnected-(U5A-PA11{slash}TIM1_CH4{slash}SPI1_MISO{slash}CAN1_RX-Pad44)") (class "Default")
      (node (ref "U5") (pin "44") (pinfunction "PA11/TIM1_CH4/SPI1_MISO/CAN1_RX_44") (pintype "passive"))
    )
    (net (code "103") (name "unconnected-(U5A-PA12{slash}SPI1_MOSI{slash}CAN1_TX{slash}TIM1_ETR{slash}U1_485_DIR-Pad45)") (class "Default")
      (node (ref "U5") (pin "45") (pinfunction "PA12/SPI1_MOSI/CAN1_TX/TIM1_ETR/U1_485_DIR_45") (pintype "passive"))
    )
    (net (code "104") (name "unconnected-(U5A-PA15{slash}JTDI{slash}TIM2_CH1{slash}USART2_RX{slash}SPI1_NSS{slash}SPI3_NSS-Pad50)") (class "Default")
      (node (ref "U5") (pin "50") (pinfunction "PA15/JTDI/TIM2_CH1/USART2_RX/SPI1_NSS/SPI3_NSS_50") (pintype "passive"))
    )
    (net (code "105") (name "unconnected-(U5A-PC6{slash}TSC_G4_IO1{slash}SDMMC1_D6-Pad37)") (class "Default")
      (node (ref "U5") (pin "37") (pinfunction "PC6/TSC_G4_IO1/SDMMC1_D6_37") (pintype "passive"))
    )
    (net (code "106") (name "unconnected-(U5A-PC7{slash}TSC_G4_IO2{slash}SDMMC1_D7-Pad38)") (class "Default")
      (node (ref "U5") (pin "38") (pinfunction "PC7/TSC_G4_IO2/SDMMC1_D7_38") (pintype "passive"))
    )
    (net (code "107") (name "unconnected-(U5A-PC14_-_OSC32_IN-Pad3)") (class "Default")
      (node (ref "U5") (pin "3") (pinfunction "PC14_-_OSC32_IN_3") (pintype "passive"))
    )
    (net (code "108") (name "unconnected-(U5A-PC15_-_OSC32_OUT-Pad4)") (class "Default")
      (node (ref "U5") (pin "4") (pinfunction "PC15_-_OSC32_OUT_4") (pintype "passive"))
    )
    (net (code "109") (name "unconnected-(U5A-PVD_IN{slash}USART1_RX{slash}I2C1_SDA{slash}LPTIM1_IN2{slash}PB7-Pad59)") (class "Default")
      (node (ref "U5") (pin "59") (pinfunction "PVD_IN/USART1_RX/I2C1_SDA/LPTIM1_IN2/PB7_59") (pintype "passive"))
    )
    (net (code "110") (name "unconnected-(U5A-RTC_TAMP1{slash}WKUP2{slash}PC13{slash}RTC_OUT-Pad2)") (class "Default")
      (node (ref "U5") (pin "2") (pinfunction "RTC_TAMP1/WKUP2/PC13/RTC_OUT_2") (pintype "passive"))
    )
    (net (code "111") (name "unconnected-(U5A-SDMMC1_D5{slash}CAN1_TX{slash}SPI2_NSS{slash}I2C1_SDA{slash}IR_OUT{slash}PB9-Pad62)") (class "Default")
      (node (ref "U5") (pin "62") (pinfunction "SDMMC1_D5/CAN1_TX/SPI2_NSS/I2C1_SDA/IR_OUT/PB9_62") (pintype "passive"))
    )
    (net (code "112") (name "unconnected-(U5A-TIM16_CH1N{slash}USART1_TX{slash}I2C1_SCL{slash}LPTIM1_ETR{slash}PB6-Pad58)") (class "Default")
      (node (ref "U5") (pin "58") (pinfunction "TIM16_CH1N/USART1_TX/I2C1_SCL/LPTIM1_ETR/PB6_58") (pintype "passive"))
    )
    (net (code "113") (name "unconnected-(U5A-TIM16_CH1{slash}SDMMC1_D4{slash}CAN1_RX{slash}I2C1_SCL{slash}PB8-Pad61)") (class "Default")
      (node (ref "U5") (pin "61") (pinfunction "TIM16_CH1/SDMMC1_D4/CAN1_RX/I2C1_SCL/PB8_61") (pintype "passive"))
    )
    (net (code "114") (name "unconnected-(U5A-USART1_CK{slash}SPI1_MOSI{slash}I2C1_SMBA{slash}LPTIM1_IN1{slash}PB5-Pad57)") (class "Default")
      (node (ref "U5") (pin "57") (pinfunction "USART1_CK/SPI1_MOSI/I2C1_SMBA/LPTIM1_IN1/PB5_57") (pintype "passive"))
    )
  )
)
